# 4040M_V1_0.net
KiCad netlist of a schematic drawn in EasyEDA Pro
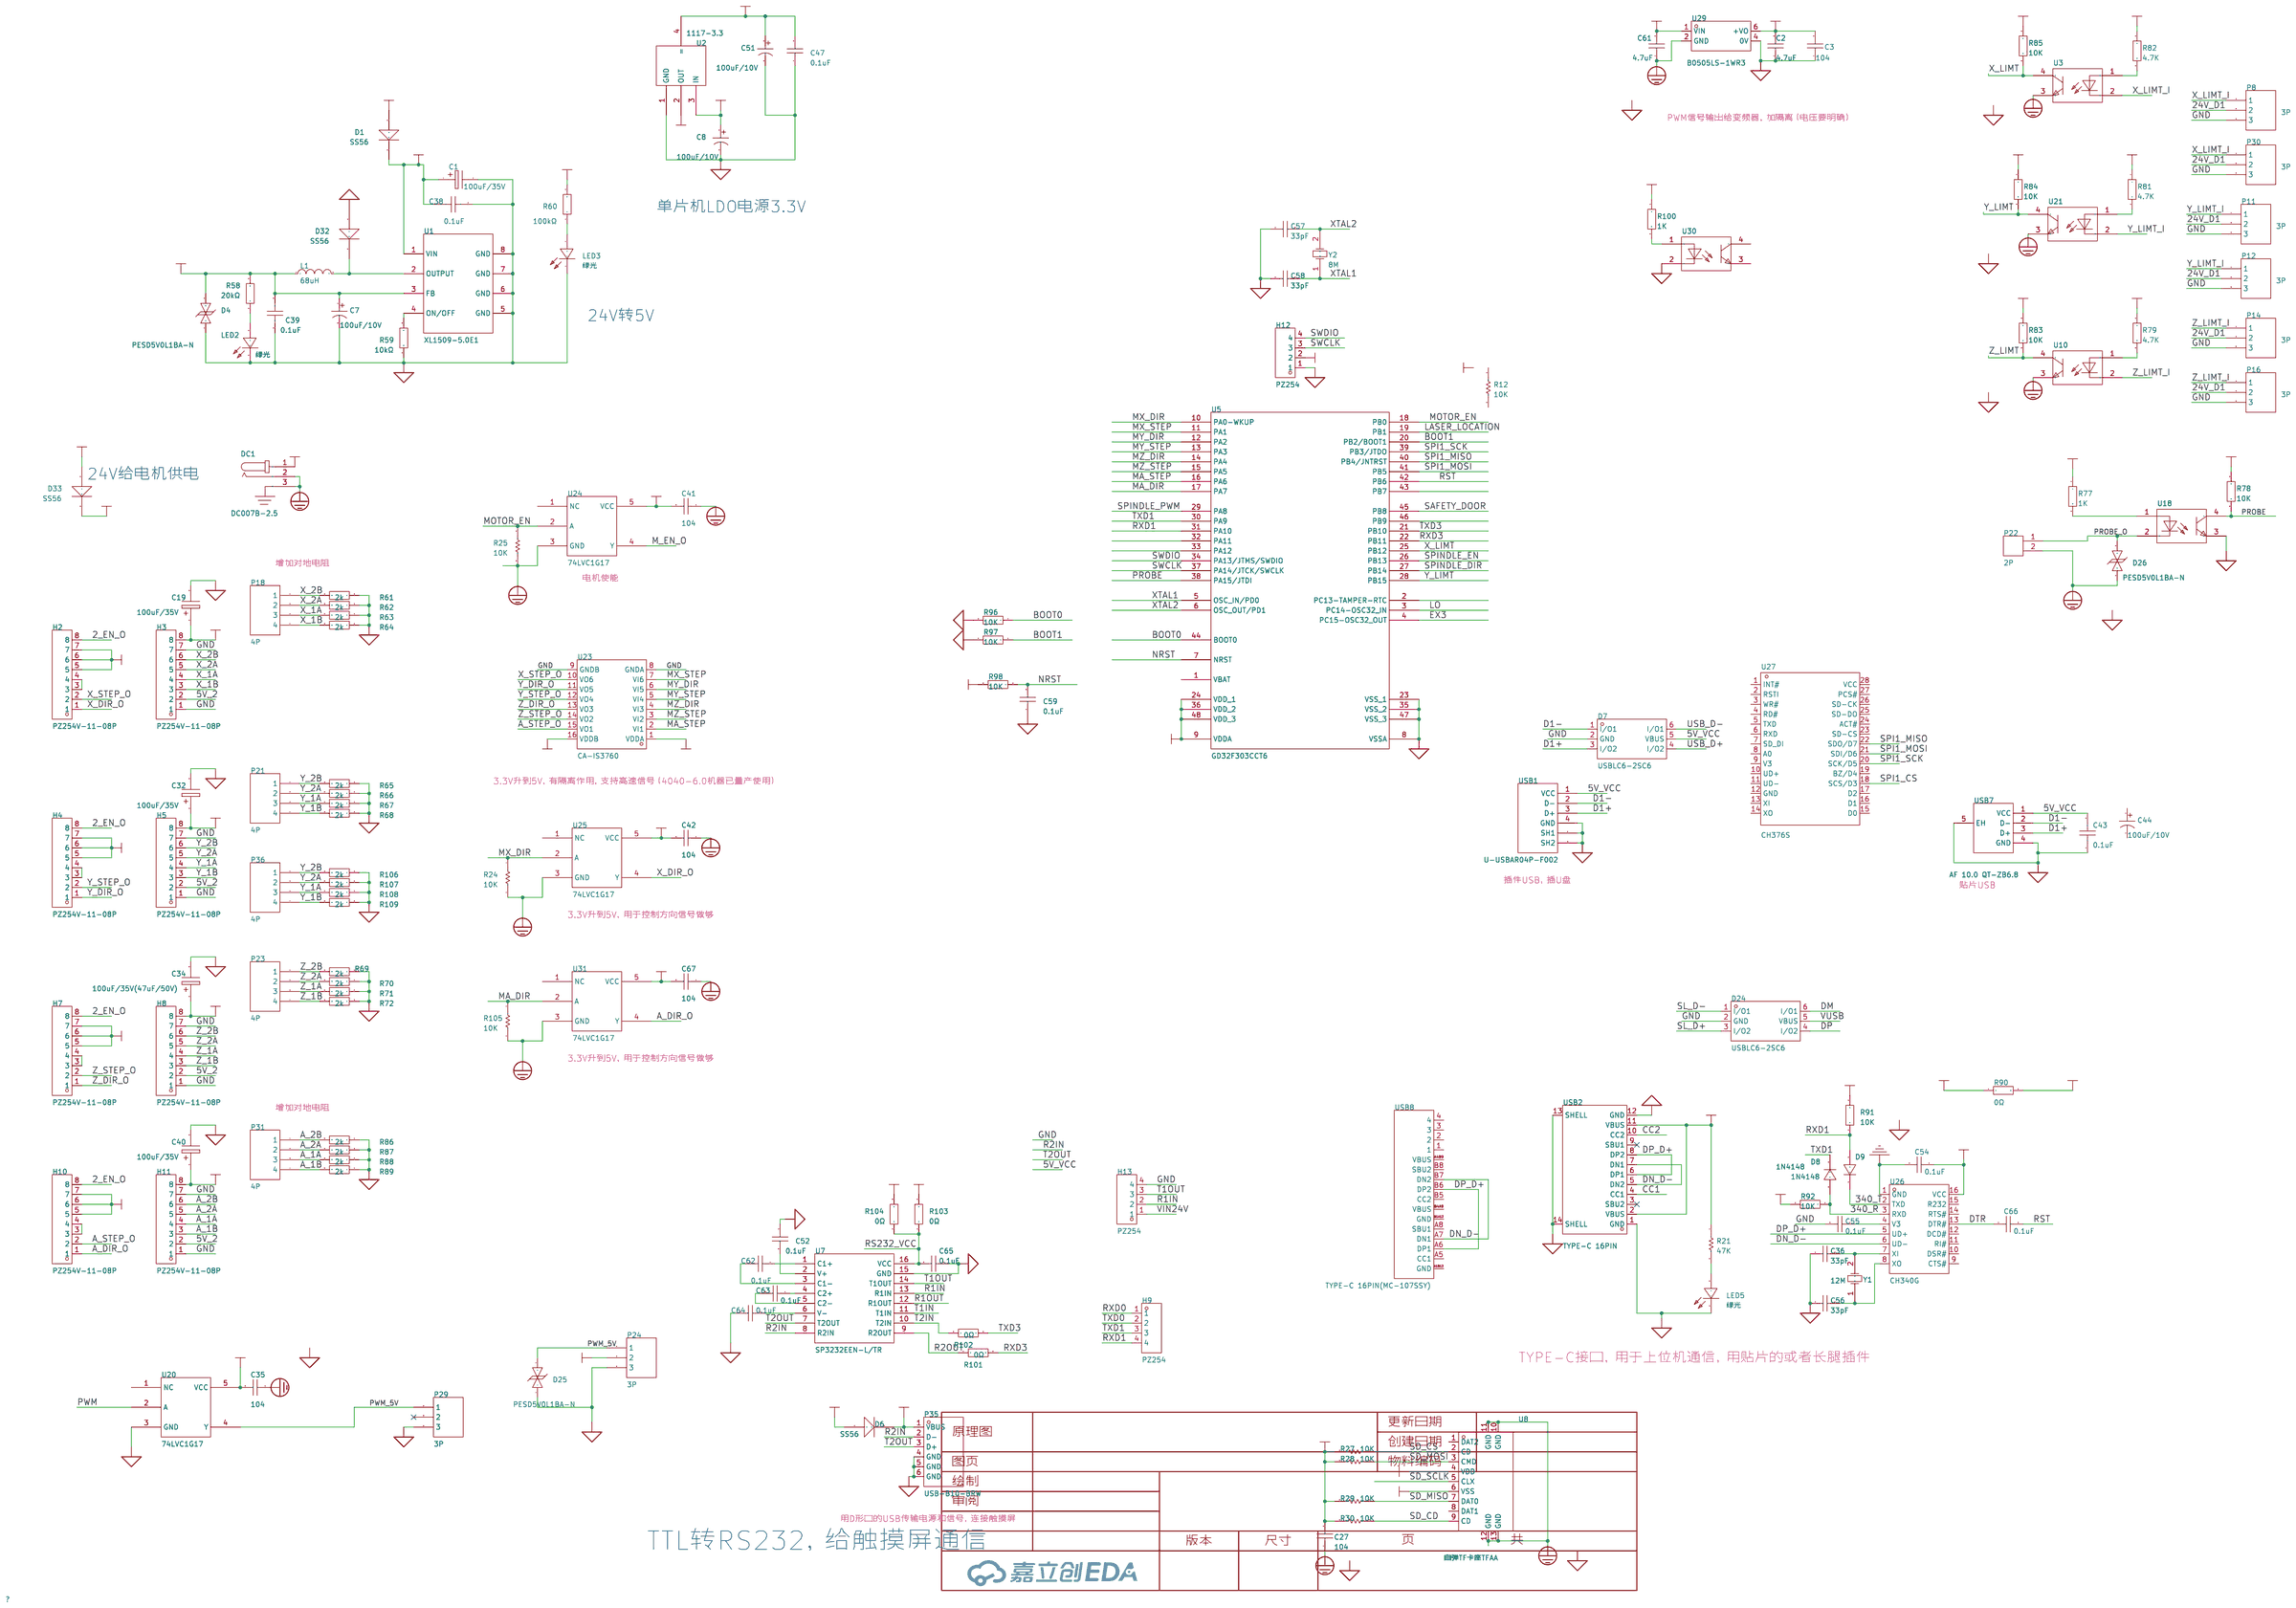
[diagram p0: schematic sheet]

(export (version "E")
  (design (tool "Eeschema 10.0.6"))
  (components
    (comp (ref "C1")
      (value "100uF/35V")
      (footprint "easyedapro:电解电容贴片10x10")
      (libsource (lib "easyedapro") (part "ELECTRO1"))
    )
    (comp (ref "C2") (value "4.7uF") (libsource (lib "easyedapro") (part "CAP")))
    (comp (ref "C3") (value "104") (libsource (lib "easyedapro") (part "CAP")))
    (comp (ref "C7")
      (value "100uF/10V")
      (footprint "easyedapro:CAP-SMD_BD5.0-L5.3-W5.3-RD")
      (fields (field (name "Manufacturer Part") "CS1A101M-CRD54") (field (name "Manufacturer") "ST(先科)"))
      (libsource (lib "easyedapro") (part "CS1A101M-CRD54"))
    )
    (comp (ref "C8")
      (value "100uF/10V")
      (footprint "easyedapro:CAP-SMD_BD5.0-L5.3-W5.3-RD")
      (fields (field (name "Manufacturer Part") "CS1A101M-CRD54") (field (name "Manufacturer") "ST(先科)"))
      (libsource (lib "easyedapro") (part "CS1A101M-CRD54"))
    )
    (comp (ref "C19")
      (value "100uF/35V")
      (footprint "easyedapro:电解电容贴片10x10")
      (libsource (lib "easyedapro") (part "ELECTRO1"))
    )
    (comp (ref "C27")
      (value "104")
      (footprint "easyedapro:11")
      (description "Capacitor (Semiconductor SIM Model)")
      (libsource (lib "easyedapro") (part "Cap Semi"))
    )
    (comp (ref "C32")
      (value "100uF/35V")
      (footprint "easyedapro:电解电容贴片10x10")
      (libsource (lib "easyedapro") (part "ELECTRO1"))
    )
    (comp (ref "C34")
      (value "100uF/35V(47uF/50V)")
      (footprint "easyedapro:电解电容贴片10x10")
      (libsource (lib "easyedapro") (part "ELECTRO1"))
    )
    (comp (ref "C35")
      (value "104")
      (footprint "easyedapro:0603C")
      (description "Capacitor (Semiconductor SIM Model)")
      (libsource (lib "easyedapro") (part "Cap Semi"))
    )
    (comp (ref "C36")
      (value "33pF")
      (footprint "easyedapro:C0603")
      (description "容值:12pF;精度:±5%;额定电压:50V;温度系数:C0G;")
      (fields
        (field (name "Manufacturer Part") "CL10C120JB8NNNC")
        (field (name "Manufacturer") "SAMSUNG(三星)")
      )
      (libsource (lib "easyedapro") (part "CL10C120JB8NNNC"))
    )
    (comp (ref "C38")
      (value "0.1uF")
      (footprint "easyedapro:C0603")
      (description "容值:8.2nF;精度:±10%;额定电压:50V;温度系数:X7R;")
      (fields (field (name "Manufacturer Part") "0603B822K500NT") (field (name "Manufacturer") "FH(风华)"))
      (libsource (lib "easyedapro") (part "0603B822K500NT"))
    )
    (comp (ref "C39")
      (value "0.1uF")
      (footprint "easyedapro:C0603")
      (description "容值:8.2nF;精度:±10%;额定电压:50V;温度系数:X7R;")
      (fields (field (name "Manufacturer Part") "0603B822K500NT") (field (name "Manufacturer") "FH(风华)"))
      (libsource (lib "easyedapro") (part "0603B822K500NT"))
    )
    (comp (ref "C40")
      (value "100uF/35V")
      (footprint "easyedapro:电解电容贴片10x10")
      (libsource (lib "easyedapro") (part "ELECTRO1"))
    )
    (comp (ref "C41")
      (value "104")
      (footprint "easyedapro:0603C")
      (description "Capacitor (Semiconductor SIM Model)")
      (libsource (lib "easyedapro") (part "Cap Semi"))
    )
    (comp (ref "C42")
      (value "104")
      (footprint "easyedapro:0603C")
      (description "Capacitor (Semiconductor SIM Model)")
      (libsource (lib "easyedapro") (part "Cap Semi"))
    )
    (comp (ref "C43")
      (value "0.1uF")
      (footprint "easyedapro:C0603")
      (description "容值:8.2nF;精度:±10%;额定电压:50V;温度系数:X7R;")
      (fields (field (name "Manufacturer Part") "0603B822K500NT") (field (name "Manufacturer") "FH(风华)"))
      (libsource (lib "easyedapro") (part "0603B822K500NT"))
    )
    (comp (ref "C44")
      (value "100uF/10V")
      (footprint "easyedapro:CAP-SMD_BD5.0-L5.3-W5.3-RD")
      (fields (field (name "Manufacturer Part") "CS1A101M-CRD54") (field (name "Manufacturer") "ST(先科)"))
      (libsource (lib "easyedapro") (part "CS1A101M-CRD54"))
    )
    (comp (ref "C47")
      (value "0.1uF")
      (footprint "easyedapro:C0603")
      (description "容值:6.8nF;精度:±10%;额定电压:50V;温度系数:X7R;")
      (fields (field (name "Manufacturer Part") "0603B682K500NT") (field (name "Manufacturer") "FH(风华)"))
      (libsource (lib "easyedapro") (part "0603B682K500NT"))
    )
    (comp (ref "C51")
      (value "100uF/10V")
      (footprint "easyedapro:CAP-SMD_BD5.0-L5.3-W5.3-RD")
      (fields (field (name "Manufacturer Part") "CS1A101M-CRD54") (field (name "Manufacturer") "ST(先科)"))
      (libsource (lib "easyedapro") (part "CS1A101M-CRD54"))
    )
    (comp (ref "C52")
      (value "0.1uF")
      (footprint "easyedapro:C0603")
      (description "容值:6.8nF;精度:±10%;额定电压:50V;温度系数:X7R;")
      (fields (field (name "Manufacturer Part") "0603B682K500NT") (field (name "Manufacturer") "FH(风华)"))
      (libsource (lib "easyedapro") (part "0603B682K500NT"))
    )
    (comp (ref "C54")
      (value "0.1uF")
      (footprint "easyedapro:C0603")
      (description "容值:6.8nF;精度:±10%;额定电压:50V;温度系数:X7R;")
      (fields (field (name "Manufacturer Part") "0603B682K500NT") (field (name "Manufacturer") "FH(风华)"))
      (libsource (lib "easyedapro") (part "0603B682K500NT"))
    )
    (comp (ref "C55")
      (value "0.1uF")
      (footprint "easyedapro:C0603")
      (description "容值:6.8nF;精度:±10%;额定电压:50V;温度系数:X7R;")
      (fields (field (name "Manufacturer Part") "0603B682K500NT") (field (name "Manufacturer") "FH(风华)"))
      (libsource (lib "easyedapro") (part "0603B682K500NT"))
    )
    (comp (ref "C56")
      (value "33pF")
      (footprint "easyedapro:C0603")
      (description "容值:12pF;精度:±5%;额定电压:50V;温度系数:C0G;")
      (fields
        (field (name "Manufacturer Part") "CL10C120JB8NNNC")
        (field (name "Manufacturer") "SAMSUNG(三星)")
      )
      (libsource (lib "easyedapro") (part "CL10C120JB8NNNC"))
    )
    (comp (ref "C57")
      (value "33pF")
      (footprint "easyedapro:C0603")
      (description "容值:12pF;精度:±5%;额定电压:50V;温度系数:C0G;")
      (fields
        (field (name "Manufacturer Part") "CL10C120JB8NNNC")
        (field (name "Manufacturer") "SAMSUNG(三星)")
      )
      (libsource (lib "easyedapro") (part "CL10C120JB8NNNC"))
    )
    (comp (ref "C58")
      (value "33pF")
      (footprint "easyedapro:C0603")
      (description "容值:12pF;精度:±5%;额定电压:50V;温度系数:C0G;")
      (fields
        (field (name "Manufacturer Part") "CL10C120JB8NNNC")
        (field (name "Manufacturer") "SAMSUNG(三星)")
      )
      (libsource (lib "easyedapro") (part "CL10C120JB8NNNC"))
    )
    (comp (ref "C59")
      (value "0.1uF")
      (footprint "easyedapro:C0603")
      (description "容值:6.8nF;精度:±10%;额定电压:50V;温度系数:X7R;")
      (fields (field (name "Manufacturer Part") "0603B682K500NT") (field (name "Manufacturer") "FH(风华)"))
      (libsource (lib "easyedapro") (part "0603B682K500NT"))
    )
    (comp (ref "C61") (value "4.7uF") (libsource (lib "easyedapro") (part "CAP")))
    (comp (ref "C62")
      (value "0.1uF")
      (footprint "easyedapro:C0603")
      (description "容值:6.8nF;精度:±10%;额定电压:50V;温度系数:X7R;")
      (fields (field (name "Manufacturer Part") "0603B682K500NT") (field (name "Manufacturer") "FH(风华)"))
      (libsource (lib "easyedapro") (part "0603B682K500NT"))
    )
    (comp (ref "C63")
      (value "0.1uF")
      (footprint "easyedapro:C0603")
      (description "容值:6.8nF;精度:±10%;额定电压:50V;温度系数:X7R;")
      (fields (field (name "Manufacturer Part") "0603B682K500NT") (field (name "Manufacturer") "FH(风华)"))
      (libsource (lib "easyedapro") (part "0603B682K500NT"))
    )
    (comp (ref "C64")
      (value "0.1uF")
      (footprint "easyedapro:C0603")
      (description "容值:6.8nF;精度:±10%;额定电压:50V;温度系数:X7R;")
      (fields (field (name "Manufacturer Part") "0603B682K500NT") (field (name "Manufacturer") "FH(风华)"))
      (libsource (lib "easyedapro") (part "0603B682K500NT"))
    )
    (comp (ref "C65")
      (value "0.1uF")
      (footprint "easyedapro:C0603")
      (description "容值:6.8nF;精度:±10%;额定电压:50V;温度系数:X7R;")
      (fields (field (name "Manufacturer Part") "0603B682K500NT") (field (name "Manufacturer") "FH(风华)"))
      (libsource (lib "easyedapro") (part "0603B682K500NT"))
    )
    (comp (ref "C66")
      (value "0.1uF")
      (footprint "easyedapro:C0603")
      (description "容值:6.8nF;精度:±10%;额定电压:50V;温度系数:X7R;")
      (fields (field (name "Manufacturer Part") "0603B682K500NT") (field (name "Manufacturer") "FH(风华)"))
      (libsource (lib "easyedapro") (part "0603B682K500NT"))
    )
    (comp (ref "C67")
      (value "104")
      (footprint "easyedapro:0603C")
      (description "Capacitor (Semiconductor SIM Model)")
      (libsource (lib "easyedapro") (part "Cap Semi"))
    )
    (comp (ref "D1")
      (value "SS56")
      (footprint "easyedapro:SMA")
      (libsource (lib "easyedapro") (part "1N4148"))
    )
    (comp (ref "D4")
      (value "PESD5V0L1BA-N")
      (footprint "easyedapro:SOD-523_L1.2-W0.8-LS1.6-BI")
      (description "极性:Bidirectional;反向关断电压（典型值）:5V (Max);击穿电压（最小值）:6V;箝位电压:15V;峰值脉冲电流（10/1000us）:5A (8/20us);")
      (fields (field (name "Manufacturer") "BORN伯恩半导体"))
      (libsource (lib "easyedapro") (part "PESD5V0S1BBN"))
    )
    (comp (ref "D6")
      (value "SS56")
      (footprint "easyedapro:SMA")
      (libsource (lib "easyedapro") (part "1N4148"))
    )
    (comp (ref "D7")
      (value "USBLC6-2SC6")
      (footprint "easyedapro:SOT-23-6_L2.9-W1.6-P0.95-LS2.8-BL")
      (description "最大钳位电压:15V;击穿电压:6V;")
      (fields (field (name "Manufacturer") "UMW(友台半导体)"))
      (libsource (lib "easyedapro") (part "USBLC6-2SC6_C2687116"))
    )
    (comp (ref "D8")
      (value "1N4148")
      (footprint "easyedapro:SOD-323_L1.8-W1.3-LS2.5-RD")
      (description "二极管配置:独立式;正向压降(Vf):1.25V@150mA;直流反向耐压(Vr):100V;整流电流:150mA;反向恢复时间(Trr):4ns;")
      (fields (field (name "Manufacturer") "CJ(江苏长电/长晶)"))
      (libsource (lib "easyedapro") (part "1N4148WS T4"))
    )
    (comp (ref "D9")
      (value "1N4148")
      (footprint "easyedapro:SOD-323_L1.8-W1.3-LS2.5-RD")
      (description "二极管配置:独立式;正向压降(Vf):1.25V@150mA;直流反向耐压(Vr):100V;整流电流:150mA;反向恢复时间(Trr):4ns;")
      (fields (field (name "Manufacturer") "CJ(江苏长电/长晶)"))
      (libsource (lib "easyedapro") (part "1N4148WS T4"))
    )
    (comp (ref "D24")
      (value "USBLC6-2SC6")
      (footprint "easyedapro:SOT-23-6_L2.9-W1.6-P0.95-LS2.8-BL")
      (description "最大钳位电压:15V;击穿电压:6V;")
      (fields (field (name "Manufacturer") "UMW(友台半导体)"))
      (libsource (lib "easyedapro") (part "USBLC6-2SC6_C2687116"))
    )
    (comp (ref "D25")
      (value "PESD5V0L1BA-N")
      (footprint "easyedapro:SOD-523_L1.2-W0.8-LS1.6-BI")
      (description "极性:Bidirectional;反向关断电压（典型值）:5V (Max);击穿电压（最小值）:6V;箝位电压:15V;峰值脉冲电流（10/1000us）:5A (8/20us);")
      (fields (field (name "Manufacturer") "BORN伯恩半导体"))
      (libsource (lib "easyedapro") (part "PESD5V0S1BBN"))
    )
    (comp (ref "D26")
      (value "PESD5V0L1BA-N")
      (footprint "easyedapro:SOD-523_L1.2-W0.8-LS1.6-BI")
      (description "极性:Bidirectional;反向关断电压（典型值）:5V (Max);击穿电压（最小值）:6V;箝位电压:15V;峰值脉冲电流（10/1000us）:5A (8/20us);")
      (fields (field (name "Manufacturer") "BORN伯恩半导体"))
      (libsource (lib "easyedapro") (part "PESD5V0S1BBN"))
    )
    (comp (ref "D32")
      (value "SS56")
      (footprint "easyedapro:SMA")
      (libsource (lib "easyedapro") (part "1N4148"))
    )
    (comp (ref "D33")
      (value "SS56")
      (footprint "easyedapro:SMA")
      (libsource (lib "easyedapro") (part "1N4148"))
    )
    (comp (ref "DC1")
      (value "DC007B-2.5")
      (footprint "easyedapro:DC-IN-TH_HX-DC007B-2.5")
      (description "连接器类型:DC电源插座;安装方式:弯插;触点内径:2.5mm;触点外径:7.7mm;额定电流:5A;额定电压:20V;工作温度:-25°C~+70°C;")
      (fields (field (name "Manufacturer") "SHOU HAN(首韩)"))
      (libsource (lib "easyedapro") (part "DC007B-2.5"))
    )
    (comp (ref "H2")
      (value "PZ254V-11-08P")
      (footprint "easyedapro:HDR-TH_8P-P2.54-V-M")
      (fields (field (name "Manufacturer") "XFCN(兴飞)"))
      (libsource (lib "easyedapro") (part "PZ254V-11-08P"))
    )
    (comp (ref "H3")
      (value "PZ254V-11-08P")
      (footprint "easyedapro:HDR-TH_8P-P2.54-V-M")
      (fields (field (name "Manufacturer") "XFCN(兴飞)"))
      (libsource (lib "easyedapro") (part "PZ254V-11-08P"))
    )
    (comp (ref "H4")
      (value "PZ254V-11-08P")
      (footprint "easyedapro:HDR-TH_8P-P2.54-V-M")
      (fields (field (name "Manufacturer") "XFCN(兴飞)"))
      (libsource (lib "easyedapro") (part "PZ254V-11-08P"))
    )
    (comp (ref "H5")
      (value "PZ254V-11-08P")
      (footprint "easyedapro:HDR-TH_8P-P2.54-V-M")
      (fields (field (name "Manufacturer") "XFCN(兴飞)"))
      (libsource (lib "easyedapro") (part "PZ254V-11-08P"))
    )
    (comp (ref "H7")
      (value "PZ254V-11-08P")
      (footprint "easyedapro:HDR-TH_8P-P2.54-V-M")
      (fields (field (name "Manufacturer") "XFCN(兴飞)"))
      (libsource (lib "easyedapro") (part "PZ254V-11-08P"))
    )
    (comp (ref "H8")
      (value "PZ254V-11-08P")
      (footprint "easyedapro:HDR-TH_8P-P2.54-V-M")
      (fields (field (name "Manufacturer") "XFCN(兴飞)"))
      (libsource (lib "easyedapro") (part "PZ254V-11-08P"))
    )
    (comp (ref "H9")
      (value "PZ254")
      (footprint "easyedapro:HDR-TH_4P-P2.54-V-M")
      (fields (field (name "Manufacturer") "XFCN(兴飞)"))
      (libsource (lib "easyedapro") (part "PZ254V-11-04P_C2691448"))
    )
    (comp (ref "H10")
      (value "PZ254V-11-08P")
      (footprint "easyedapro:HDR-TH_8P-P2.54-V-M")
      (fields (field (name "Manufacturer") "XFCN(兴飞)"))
      (libsource (lib "easyedapro") (part "PZ254V-11-08P"))
    )
    (comp (ref "H11")
      (value "PZ254V-11-08P")
      (footprint "easyedapro:HDR-TH_8P-P2.54-V-M")
      (fields (field (name "Manufacturer") "XFCN(兴飞)"))
      (libsource (lib "easyedapro") (part "PZ254V-11-08P"))
    )
    (comp (ref "H12")
      (value "PZ254")
      (footprint "easyedapro:HDR-TH_4P-P2.54-V-M")
      (fields (field (name "Manufacturer") "XFCN(兴飞)"))
      (libsource (lib "easyedapro") (part "PZ254V-11-04P_C2691448"))
    )
    (comp (ref "H13")
      (value "PZ254")
      (footprint "easyedapro:HDR-TH_4P-P2.54-V-M")
      (fields (field (name "Manufacturer") "XFCN(兴飞)"))
      (libsource (lib "easyedapro") (part "PZ254V-11-04P_C2691448"))
    )
    (comp (ref "L1")
      (value "68uH")
      (footprint "easyedapro:IND-SMD_L7.0-W7.0_SMDRI74-330MT")
      (description "电感值:33uH;精度:±20%;额定电流:960mA;饱和电流(Isat):1.8A;类型:屏蔽电感;")
      (fields (field (name "Manufacturer Part") "SMDRI74-330MT") (field (name "Manufacturer") "SXN(顺翔诺)"))
      (libsource (lib "easyedapro") (part "SMDRI74-330MT"))
    )
    (comp (ref "LED2")
      (value "绿光")
      (footprint "easyedapro:LED0603-RD")
      (fields (field (name "Manufacturer") "KENTO"))
      (libsource (lib "easyedapro") (part "KT-0603R"))
    )
    (comp (ref "LED3")
      (value "绿光")
      (footprint "easyedapro:LED0603-RD")
      (fields (field (name "Manufacturer") "KENTO"))
      (libsource (lib "easyedapro") (part "KT-0603R"))
    )
    (comp (ref "LED5")
      (value "绿光")
      (footprint "easyedapro:LED0603-RD")
      (fields (field (name "Manufacturer") "KENTO"))
      (libsource (lib "easyedapro") (part "KT-0603R"))
    )
    (comp (ref "P8")
      (value "3P")
      (footprint "easyedapro:HDR1X3_CON")
      (libsource (lib "easyedapro") (part "3P"))
    )
    (comp (ref "P11")
      (value "3P")
      (footprint "easyedapro:HDR1X3_CON")
      (libsource (lib "easyedapro") (part "3P"))
    )
    (comp (ref "P12")
      (value "3P")
      (footprint "easyedapro:HDR1X3_CON")
      (libsource (lib "easyedapro") (part "3P"))
    )
    (comp (ref "P14")
      (value "3P")
      (footprint "easyedapro:HDR1X3_CON")
      (libsource (lib "easyedapro") (part "3P"))
    )
    (comp (ref "P16")
      (value "3P")
      (footprint "easyedapro:HDR1X3_CON")
      (libsource (lib "easyedapro") (part "3P"))
    )
    (comp (ref "P18")
      (value "4P")
      (footprint "easyedapro:HDR1X4_CON")
      (libsource (lib "easyedapro") (part "4P"))
    )
    (comp (ref "P21")
      (value "4P")
      (footprint "easyedapro:HDR1X4_CON")
      (libsource (lib "easyedapro") (part "4P"))
    )
    (comp (ref "P22") (value "2P") (libsource (lib "easyedapro") (part "2P")))
    (comp (ref "P23")
      (value "4P")
      (footprint "easyedapro:HDR1X4_CON")
      (libsource (lib "easyedapro") (part "4P"))
    )
    (comp (ref "P24")
      (value "3P")
      (footprint "easyedapro:HDR1X3_CON")
      (libsource (lib "easyedapro") (part "3P"))
    )
    (comp (ref "P29")
      (value "3P")
      (footprint "easyedapro:HDR1X3_CON")
      (libsource (lib "easyedapro") (part "3P"))
    )
    (comp (ref "P30")
      (value "3P")
      (footprint "easyedapro:HDR1X3_CON")
      (libsource (lib "easyedapro") (part "3P"))
    )
    (comp (ref "P31")
      (value "4P")
      (footprint "easyedapro:HDR1X4_CON")
      (libsource (lib "easyedapro") (part "4P"))
    )
    (comp (ref "P35")
      (value "USB-B10-BRW")
      (footprint "easyedapro:USB-B-TH_USB-B10-BRW")
      (fields (field (name "Manufacturer") "XUNPU(讯普)"))
      (libsource (lib "easyedapro") (part "USB-B10-BRW"))
    )
    (comp (ref "P36")
      (value "4P")
      (footprint "easyedapro:HDR1X4_CON")
      (libsource (lib "easyedapro") (part "4P"))
    )
    (comp (ref "R12")
      (value "10K")
      (footprint "easyedapro:0603R")
      (description "Resistor")
      (libsource (lib "") (part "RES_1"))
    )
    (comp (ref "R21")
      (value "47K")
      (footprint "easyedapro:10")
      (description "Resistor")
      (libsource (lib "") (part "RES_1"))
    )
    (comp (ref "R24")
      (value "10K")
      (description "Resistor")
      (fields (field (name "Publisher") "Altium Limited"))
      (libsource (lib "easyedapro") (part "RES"))
    )
    (comp (ref "R25")
      (value "10K")
      (description "Resistor")
      (fields (field (name "Publisher") "Altium Limited"))
      (libsource (lib "easyedapro") (part "RES"))
    )
    (comp (ref "R27")
      (value "10K")
      (footprint "easyedapro:10")
      (description "Resistor")
      (libsource (lib "") (part "RES_1"))
    )
    (comp (ref "R28")
      (value "10K")
      (footprint "easyedapro:10")
      (description "Resistor")
      (libsource (lib "") (part "RES_1"))
    )
    (comp (ref "R29")
      (value "10K")
      (footprint "easyedapro:10")
      (description "Resistor")
      (libsource (lib "") (part "RES_1"))
    )
    (comp (ref "R30")
      (value "10K")
      (footprint "easyedapro:10")
      (description "Resistor")
      (libsource (lib "") (part "RES_1"))
    )
    (comp (ref "R58")
      (value "20kΩ")
      (footprint "easyedapro:R0603")
      (description "电阻类型:厚膜电阻;阻值:24kΩ;精度:±1%;功率:100mW;工作电压:75V;温度系数:±100ppm/°C;")
      (fields
        (field (name "Manufacturer Part") "0603WAF2402T5E")
        (field (name "Manufacturer") "UNI-ROYAL(厚声)")
      )
      (libsource (lib "easyedapro") (part "0603WAF2402T5E"))
    )
    (comp (ref "R59")
      (value "10kΩ")
      (footprint "easyedapro:R0603")
      (description "电阻类型:厚膜电阻;阻值:24kΩ;精度:±1%;功率:100mW;工作电压:75V;温度系数:±100ppm/°C;")
      (fields
        (field (name "Manufacturer Part") "0603WAF2402T5E")
        (field (name "Manufacturer") "UNI-ROYAL(厚声)")
      )
      (libsource (lib "easyedapro") (part "0603WAF2402T5E"))
    )
    (comp (ref "R60")
      (value "100kΩ")
      (footprint "easyedapro:R0603")
      (description "电阻类型:厚膜电阻;阻值:24kΩ;精度:±1%;功率:100mW;工作电压:75V;温度系数:±100ppm/°C;")
      (fields
        (field (name "Manufacturer Part") "0603WAF2402T5E")
        (field (name "Manufacturer") "UNI-ROYAL(厚声)")
      )
      (libsource (lib "easyedapro") (part "0603WAF2402T5E"))
    )
    (comp (ref "R61")
      (value "2k")
      (footprint "easyedapro:R0603")
      (description "电阻类型:厚膜电阻;阻值:24kΩ;精度:±1%;功率:100mW;工作电压:75V;温度系数:±100ppm/°C;")
      (fields
        (field (name "Manufacturer Part") "0603WAF2402T5E")
        (field (name "Manufacturer") "UNI-ROYAL(厚声)")
      )
      (libsource (lib "easyedapro") (part "0603WAF2402T5E"))
    )
    (comp (ref "R62")
      (value "2k")
      (footprint "easyedapro:R0603")
      (description "电阻类型:厚膜电阻;阻值:24kΩ;精度:±1%;功率:100mW;工作电压:75V;温度系数:±100ppm/°C;")
      (fields
        (field (name "Manufacturer Part") "0603WAF2402T5E")
        (field (name "Manufacturer") "UNI-ROYAL(厚声)")
      )
      (libsource (lib "easyedapro") (part "0603WAF2402T5E"))
    )
    (comp (ref "R63")
      (value "2k")
      (footprint "easyedapro:R0603")
      (description "电阻类型:厚膜电阻;阻值:24kΩ;精度:±1%;功率:100mW;工作电压:75V;温度系数:±100ppm/°C;")
      (fields
        (field (name "Manufacturer Part") "0603WAF2402T5E")
        (field (name "Manufacturer") "UNI-ROYAL(厚声)")
      )
      (libsource (lib "easyedapro") (part "0603WAF2402T5E"))
    )
    (comp (ref "R64")
      (value "2k")
      (footprint "easyedapro:R0603")
      (description "电阻类型:厚膜电阻;阻值:24kΩ;精度:±1%;功率:100mW;工作电压:75V;温度系数:±100ppm/°C;")
      (fields
        (field (name "Manufacturer Part") "0603WAF2402T5E")
        (field (name "Manufacturer") "UNI-ROYAL(厚声)")
      )
      (libsource (lib "easyedapro") (part "0603WAF2402T5E"))
    )
    (comp (ref "R65")
      (value "2k")
      (footprint "easyedapro:R0603")
      (description "电阻类型:厚膜电阻;阻值:24kΩ;精度:±1%;功率:100mW;工作电压:75V;温度系数:±100ppm/°C;")
      (fields
        (field (name "Manufacturer Part") "0603WAF2402T5E")
        (field (name "Manufacturer") "UNI-ROYAL(厚声)")
      )
      (libsource (lib "easyedapro") (part "0603WAF2402T5E"))
    )
    (comp (ref "R66")
      (value "2k")
      (footprint "easyedapro:R0603")
      (description "电阻类型:厚膜电阻;阻值:24kΩ;精度:±1%;功率:100mW;工作电压:75V;温度系数:±100ppm/°C;")
      (fields
        (field (name "Manufacturer Part") "0603WAF2402T5E")
        (field (name "Manufacturer") "UNI-ROYAL(厚声)")
      )
      (libsource (lib "easyedapro") (part "0603WAF2402T5E"))
    )
    (comp (ref "R67")
      (value "2k")
      (footprint "easyedapro:R0603")
      (description "电阻类型:厚膜电阻;阻值:24kΩ;精度:±1%;功率:100mW;工作电压:75V;温度系数:±100ppm/°C;")
      (fields
        (field (name "Manufacturer Part") "0603WAF2402T5E")
        (field (name "Manufacturer") "UNI-ROYAL(厚声)")
      )
      (libsource (lib "easyedapro") (part "0603WAF2402T5E"))
    )
    (comp (ref "R68")
      (value "2k")
      (footprint "easyedapro:R0603")
      (description "电阻类型:厚膜电阻;阻值:24kΩ;精度:±1%;功率:100mW;工作电压:75V;温度系数:±100ppm/°C;")
      (fields
        (field (name "Manufacturer Part") "0603WAF2402T5E")
        (field (name "Manufacturer") "UNI-ROYAL(厚声)")
      )
      (libsource (lib "easyedapro") (part "0603WAF2402T5E"))
    )
    (comp (ref "R69")
      (value "2k")
      (footprint "easyedapro:R0603")
      (description "电阻类型:厚膜电阻;阻值:24kΩ;精度:±1%;功率:100mW;工作电压:75V;温度系数:±100ppm/°C;")
      (fields
        (field (name "Manufacturer Part") "0603WAF2402T5E")
        (field (name "Manufacturer") "UNI-ROYAL(厚声)")
      )
      (libsource (lib "easyedapro") (part "0603WAF2402T5E"))
    )
    (comp (ref "R70")
      (value "2k")
      (footprint "easyedapro:R0603")
      (description "电阻类型:厚膜电阻;阻值:24kΩ;精度:±1%;功率:100mW;工作电压:75V;温度系数:±100ppm/°C;")
      (fields
        (field (name "Manufacturer Part") "0603WAF2402T5E")
        (field (name "Manufacturer") "UNI-ROYAL(厚声)")
      )
      (libsource (lib "easyedapro") (part "0603WAF2402T5E"))
    )
    (comp (ref "R71")
      (value "2k")
      (footprint "easyedapro:R0603")
      (description "电阻类型:厚膜电阻;阻值:24kΩ;精度:±1%;功率:100mW;工作电压:75V;温度系数:±100ppm/°C;")
      (fields
        (field (name "Manufacturer Part") "0603WAF2402T5E")
        (field (name "Manufacturer") "UNI-ROYAL(厚声)")
      )
      (libsource (lib "easyedapro") (part "0603WAF2402T5E"))
    )
    (comp (ref "R72")
      (value "2k")
      (footprint "easyedapro:R0603")
      (description "电阻类型:厚膜电阻;阻值:24kΩ;精度:±1%;功率:100mW;工作电压:75V;温度系数:±100ppm/°C;")
      (fields
        (field (name "Manufacturer Part") "0603WAF2402T5E")
        (field (name "Manufacturer") "UNI-ROYAL(厚声)")
      )
      (libsource (lib "easyedapro") (part "0603WAF2402T5E"))
    )
    (comp (ref "R77")
      (value "1K")
      (footprint "easyedapro:R0603")
      (description "电阻类型:厚膜电阻;阻值:24kΩ;精度:±1%;功率:100mW;工作电压:75V;温度系数:±100ppm/°C;")
      (fields
        (field (name "Manufacturer Part") "0603WAF2402T5E")
        (field (name "Manufacturer") "UNI-ROYAL(厚声)")
      )
      (libsource (lib "easyedapro") (part "0603WAF2402T5E"))
    )
    (comp (ref "R78")
      (value "10K")
      (footprint "easyedapro:R0603")
      (description "电阻类型:厚膜电阻;阻值:24kΩ;精度:±1%;功率:100mW;工作电压:75V;温度系数:±100ppm/°C;")
      (fields
        (field (name "Manufacturer Part") "0603WAF2402T5E")
        (field (name "Manufacturer") "UNI-ROYAL(厚声)")
      )
      (libsource (lib "easyedapro") (part "0603WAF2402T5E"))
    )
    (comp (ref "R79")
      (value "4.7K")
      (footprint "easyedapro:R0603")
      (description "电阻类型:厚膜电阻;阻值:24kΩ;精度:±1%;功率:100mW;工作电压:75V;温度系数:±100ppm/°C;")
      (fields
        (field (name "Manufacturer Part") "0603WAF2402T5E")
        (field (name "Manufacturer") "UNI-ROYAL(厚声)")
      )
      (libsource (lib "easyedapro") (part "0603WAF2402T5E"))
    )
    (comp (ref "R81")
      (value "4.7K")
      (footprint "easyedapro:R0603")
      (description "电阻类型:厚膜电阻;阻值:24kΩ;精度:±1%;功率:100mW;工作电压:75V;温度系数:±100ppm/°C;")
      (fields
        (field (name "Manufacturer Part") "0603WAF2402T5E")
        (field (name "Manufacturer") "UNI-ROYAL(厚声)")
      )
      (libsource (lib "easyedapro") (part "0603WAF2402T5E"))
    )
    (comp (ref "R82")
      (value "4.7K")
      (footprint "easyedapro:R0603")
      (description "电阻类型:厚膜电阻;阻值:24kΩ;精度:±1%;功率:100mW;工作电压:75V;温度系数:±100ppm/°C;")
      (fields
        (field (name "Manufacturer Part") "0603WAF2402T5E")
        (field (name "Manufacturer") "UNI-ROYAL(厚声)")
      )
      (libsource (lib "easyedapro") (part "0603WAF2402T5E"))
    )
    (comp (ref "R83")
      (value "47K")
      (footprint "easyedapro:R0603")
      (description "电阻类型:厚膜电阻;阻值:24kΩ;精度:±1%;功率:100mW;工作电压:75V;温度系数:±100ppm/°C;")
      (fields
        (field (name "Manufacturer Part") "0603WAF2402T5E")
        (field (name "Manufacturer") "UNI-ROYAL(厚声)")
      )
      (libsource (lib "easyedapro") (part "0603WAF2402T5E"))
    )
    (comp (ref "R84")
      (value "47K")
      (footprint "easyedapro:R0603")
      (description "电阻类型:厚膜电阻;阻值:24kΩ;精度:±1%;功率:100mW;工作电压:75V;温度系数:±100ppm/°C;")
      (fields
        (field (name "Manufacturer Part") "0603WAF2402T5E")
        (field (name "Manufacturer") "UNI-ROYAL(厚声)")
      )
      (libsource (lib "easyedapro") (part "0603WAF2402T5E"))
    )
    (comp (ref "R85")
      (value "47K")
      (footprint "easyedapro:R0603")
      (description "电阻类型:厚膜电阻;阻值:24kΩ;精度:±1%;功率:100mW;工作电压:75V;温度系数:±100ppm/°C;")
      (fields
        (field (name "Manufacturer Part") "0603WAF2402T5E")
        (field (name "Manufacturer") "UNI-ROYAL(厚声)")
      )
      (libsource (lib "easyedapro") (part "0603WAF2402T5E"))
    )
    (comp (ref "R86")
      (value "2k")
      (footprint "easyedapro:R0603")
      (description "电阻类型:厚膜电阻;阻值:24kΩ;精度:±1%;功率:100mW;工作电压:75V;温度系数:±100ppm/°C;")
      (fields
        (field (name "Manufacturer Part") "0603WAF2402T5E")
        (field (name "Manufacturer") "UNI-ROYAL(厚声)")
      )
      (libsource (lib "easyedapro") (part "0603WAF2402T5E"))
    )
    (comp (ref "R87")
      (value "2k")
      (footprint "easyedapro:R0603")
      (description "电阻类型:厚膜电阻;阻值:24kΩ;精度:±1%;功率:100mW;工作电压:75V;温度系数:±100ppm/°C;")
      (fields
        (field (name "Manufacturer Part") "0603WAF2402T5E")
        (field (name "Manufacturer") "UNI-ROYAL(厚声)")
      )
      (libsource (lib "easyedapro") (part "0603WAF2402T5E"))
    )
    (comp (ref "R88")
      (value "2k")
      (footprint "easyedapro:R0603")
      (description "电阻类型:厚膜电阻;阻值:24kΩ;精度:±1%;功率:100mW;工作电压:75V;温度系数:±100ppm/°C;")
      (fields
        (field (name "Manufacturer Part") "0603WAF2402T5E")
        (field (name "Manufacturer") "UNI-ROYAL(厚声)")
      )
      (libsource (lib "easyedapro") (part "0603WAF2402T5E"))
    )
    (comp (ref "R89")
      (value "2k")
      (footprint "easyedapro:R0603")
      (description "电阻类型:厚膜电阻;阻值:24kΩ;精度:±1%;功率:100mW;工作电压:75V;温度系数:±100ppm/°C;")
      (fields
        (field (name "Manufacturer Part") "0603WAF2402T5E")
        (field (name "Manufacturer") "UNI-ROYAL(厚声)")
      )
      (libsource (lib "easyedapro") (part "0603WAF2402T5E"))
    )
    (comp (ref "R90")
      (value "0Ω")
      (footprint "easyedapro:R0603")
      (description "电阻类型:厚膜电阻;阻值:24kΩ;精度:±1%;功率:100mW;工作电压:75V;温度系数:±100ppm/°C;")
      (fields
        (field (name "Manufacturer Part") "0603WAF2402T5E")
        (field (name "Manufacturer") "UNI-ROYAL(厚声)")
      )
      (libsource (lib "easyedapro") (part "0603WAF2402T5E"))
    )
    (comp (ref "R91")
      (value "10K")
      (footprint "easyedapro:R0603")
      (description "电阻类型:厚膜电阻;阻值:24kΩ;精度:±1%;功率:100mW;工作电压:75V;温度系数:±100ppm/°C;")
      (fields
        (field (name "Manufacturer Part") "0603WAF2402T5E")
        (field (name "Manufacturer") "UNI-ROYAL(厚声)")
      )
      (libsource (lib "easyedapro") (part "0603WAF2402T5E"))
    )
    (comp (ref "R92")
      (value "10K")
      (footprint "easyedapro:R0603")
      (description "电阻类型:厚膜电阻;阻值:24kΩ;精度:±1%;功率:100mW;工作电压:75V;温度系数:±100ppm/°C;")
      (fields
        (field (name "Manufacturer Part") "0603WAF2402T5E")
        (field (name "Manufacturer") "UNI-ROYAL(厚声)")
      )
      (libsource (lib "easyedapro") (part "0603WAF2402T5E"))
    )
    (comp (ref "R96")
      (value "10K")
      (footprint "easyedapro:R0603")
      (description "电阻类型:厚膜电阻;阻值:24kΩ;精度:±1%;功率:100mW;工作电压:75V;温度系数:±100ppm/°C;")
      (fields
        (field (name "Manufacturer Part") "0603WAF2402T5E")
        (field (name "Manufacturer") "UNI-ROYAL(厚声)")
      )
      (libsource (lib "easyedapro") (part "0603WAF2402T5E"))
    )
    (comp (ref "R97")
      (value "10K")
      (footprint "easyedapro:R0603")
      (description "电阻类型:厚膜电阻;阻值:24kΩ;精度:±1%;功率:100mW;工作电压:75V;温度系数:±100ppm/°C;")
      (fields
        (field (name "Manufacturer Part") "0603WAF2402T5E")
        (field (name "Manufacturer") "UNI-ROYAL(厚声)")
      )
      (libsource (lib "easyedapro") (part "0603WAF2402T5E"))
    )
    (comp (ref "R98")
      (value "10K")
      (footprint "easyedapro:R0603")
      (description "电阻类型:厚膜电阻;阻值:24kΩ;精度:±1%;功率:100mW;工作电压:75V;温度系数:±100ppm/°C;")
      (fields
        (field (name "Manufacturer Part") "0603WAF2402T5E")
        (field (name "Manufacturer") "UNI-ROYAL(厚声)")
      )
      (libsource (lib "easyedapro") (part "0603WAF2402T5E"))
    )
    (comp (ref "R100")
      (value "47K")
      (footprint "easyedapro:R0603")
      (description "电阻类型:厚膜电阻;阻值:24kΩ;精度:±1%;功率:100mW;工作电压:75V;温度系数:±100ppm/°C;")
      (fields
        (field (name "Manufacturer Part") "0603WAF2402T5E")
        (field (name "Manufacturer") "UNI-ROYAL(厚声)")
      )
      (libsource (lib "easyedapro") (part "0603WAF2402T5E"))
    )
    (comp (ref "R101")
      (value "0Ω")
      (footprint "easyedapro:R0603")
      (description "电阻类型:厚膜电阻;阻值:24kΩ;精度:±1%;功率:100mW;工作电压:75V;温度系数:±100ppm/°C;")
      (fields
        (field (name "Manufacturer Part") "0603WAF2402T5E")
        (field (name "Manufacturer") "UNI-ROYAL(厚声)")
      )
      (libsource (lib "easyedapro") (part "0603WAF2402T5E"))
    )
    (comp (ref "R102")
      (value "0Ω")
      (footprint "easyedapro:R0603")
      (description "电阻类型:厚膜电阻;阻值:24kΩ;精度:±1%;功率:100mW;工作电压:75V;温度系数:±100ppm/°C;")
      (fields
        (field (name "Manufacturer Part") "0603WAF2402T5E")
        (field (name "Manufacturer") "UNI-ROYAL(厚声)")
      )
      (libsource (lib "easyedapro") (part "0603WAF2402T5E"))
    )
    (comp (ref "R103")
      (value "0Ω")
      (footprint "easyedapro:R0603")
      (description "电阻类型:厚膜电阻;阻值:24kΩ;精度:±1%;功率:100mW;工作电压:75V;温度系数:±100ppm/°C;")
      (fields
        (field (name "Manufacturer Part") "0603WAF2402T5E")
        (field (name "Manufacturer") "UNI-ROYAL(厚声)")
      )
      (libsource (lib "easyedapro") (part "0603WAF2402T5E"))
    )
    (comp (ref "R104")
      (value "0Ω")
      (footprint "easyedapro:R0603")
      (description "电阻类型:厚膜电阻;阻值:24kΩ;精度:±1%;功率:100mW;工作电压:75V;温度系数:±100ppm/°C;")
      (fields
        (field (name "Manufacturer Part") "0603WAF2402T5E")
        (field (name "Manufacturer") "UNI-ROYAL(厚声)")
      )
      (libsource (lib "easyedapro") (part "0603WAF2402T5E"))
    )
    (comp (ref "R105")
      (value "10K")
      (description "Resistor")
      (fields (field (name "Publisher") "Altium Limited"))
      (libsource (lib "easyedapro") (part "RES"))
    )
    (comp (ref "R106")
      (value "2k")
      (footprint "easyedapro:R0603")
      (description "电阻类型:厚膜电阻;阻值:24kΩ;精度:±1%;功率:100mW;工作电压:75V;温度系数:±100ppm/°C;")
      (fields
        (field (name "Manufacturer Part") "0603WAF2402T5E")
        (field (name "Manufacturer") "UNI-ROYAL(厚声)")
      )
      (libsource (lib "easyedapro") (part "0603WAF2402T5E"))
    )
    (comp (ref "R107")
      (value "2k")
      (footprint "easyedapro:R0603")
      (description "电阻类型:厚膜电阻;阻值:24kΩ;精度:±1%;功率:100mW;工作电压:75V;温度系数:±100ppm/°C;")
      (fields
        (field (name "Manufacturer Part") "0603WAF2402T5E")
        (field (name "Manufacturer") "UNI-ROYAL(厚声)")
      )
      (libsource (lib "easyedapro") (part "0603WAF2402T5E"))
    )
    (comp (ref "R108")
      (value "2k")
      (footprint "easyedapro:R0603")
      (description "电阻类型:厚膜电阻;阻值:24kΩ;精度:±1%;功率:100mW;工作电压:75V;温度系数:±100ppm/°C;")
      (fields
        (field (name "Manufacturer Part") "0603WAF2402T5E")
        (field (name "Manufacturer") "UNI-ROYAL(厚声)")
      )
      (libsource (lib "easyedapro") (part "0603WAF2402T5E"))
    )
    (comp (ref "R109")
      (value "2k")
      (footprint "easyedapro:R0603")
      (description "电阻类型:厚膜电阻;阻值:24kΩ;精度:±1%;功率:100mW;工作电压:75V;温度系数:±100ppm/°C;")
      (fields
        (field (name "Manufacturer Part") "0603WAF2402T5E")
        (field (name "Manufacturer") "UNI-ROYAL(厚声)")
      )
      (libsource (lib "easyedapro") (part "0603WAF2402T5E"))
    )
    (comp (ref "U1")
      (value "XL1509-5.0E1")
      (footprint "easyedapro:SOIC-8_L5.0-W4.0-P1.27-LS6.0-BL")
      (description "功能类型:降压型;同步整流:-;输出通道数:-;拓扑结构:-;输入电压:-;输出电流(最大值):-;开关频率:-;")
      (fields (field (name "Manufacturer") "XLSEMI(芯龙)"))
      (libsource (lib "easyedapro") (part "XL1509-5.0E1"))
    )
    (comp (ref "U2")
      (value "1117-3.3")
      (footprint "easyedapro:SOT-223")
      (libsource (lib "easyedapro") (part "LM1117"))
    )
    (comp (ref "U3")
      (value "LTV-357T-C")
      (footprint "easyedapro:SOP-4_L4.4-W3.9-P2.54-LS7.0-TL")
      (fields (field (name "Manufacturer") "LITEON(光宝)"))
      (libsource (lib "easyedapro") (part "LTV-357T-C"))
    )
    (comp (ref "U5")
      (value "GD32F303CCT6")
      (footprint "easyedapro:LQFP48")
      (description "STM32 ARM-based 32-bit MCU with 32 Kbytes Flash, 48-pin LQFP, Industrial Temperature")
      (libsource (lib "easyedapro") (part "STM32F103C6T6"))
    )
    (comp (ref "U7")
      (value "SP3232EEN-L/TR")
      (footprint "easyedapro:SOIC-16_L9.9-W3.9-P1.27-LS6.0-BL")
      (description "类型:收发器;数据速率:235Kbps;")
      (fields (field (name "Manufacturer") "MaxLinear(迈凌)"))
      (libsource (lib "easyedapro") (part "SP3232EEN-L/TR"))
    )
    (comp (ref "U8")
      (value "自弹TF卡座TFAA")
      (footprint "easyedapro:SIM-SMD_C9900015645")
      (libsource (lib "easyedapro") (part "自弹TF卡座TFAA"))
    )
    (comp (ref "U10")
      (value "LTV-357T-C")
      (footprint "easyedapro:SOP-4_L4.4-W3.9-P2.54-LS7.0-TL")
      (fields (field (name "Manufacturer") "LITEON(光宝)"))
      (libsource (lib "easyedapro") (part "LTV-357T-C"))
    )
    (comp (ref "U18")
      (value "LTV-357T-C")
      (footprint "easyedapro:SOP-4_L4.4-W3.9-P2.54-LS7.0-TL")
      (fields (field (name "Manufacturer") "LITEON(光宝)"))
      (libsource (lib "easyedapro") (part "LTV-357T-C"))
    )
    (comp (ref "U20")
      (value "74LVC1G17")
      (footprint "easyedapro:SMD8")
      (libsource (lib "easyedapro") (part "74LVC1G04"))
    )
    (comp (ref "U21")
      (value "LTV-357T-C")
      (footprint "easyedapro:SOP-4_L4.4-W3.9-P2.54-LS7.0-TL")
      (fields (field (name "Manufacturer") "LITEON(光宝)"))
      (libsource (lib "easyedapro") (part "LTV-357T-C"))
    )
    (comp (ref "U23")
      (value "CA-IS3760")
      (footprint "easyedapro:SOIC-16_L9.9-W3.9-P1.27-LS6.0-BL")
      (fields (field (name "Manufacturer") "Chipanalog(川土微)"))
      (libsource (lib "easyedapro") (part "CA-IS3760HN"))
    )
    (comp (ref "U24")
      (value "74LVC1G17")
      (footprint "easyedapro:SMD8")
      (libsource (lib "easyedapro") (part "74LVC1G04"))
    )
    (comp (ref "U25")
      (value "74LVC1G17")
      (footprint "easyedapro:SMD8")
      (libsource (lib "easyedapro") (part "74LVC1G04"))
    )
    (comp (ref "U26")
      (value "CH340G")
      (footprint "easyedapro:SOIC-16_L9.9-W3.9-P1.27-LS6.0-BL")
      (description "应用功能:收发器;接口协议:USB 2.0;数据速率:2Mbps;")
      (fields (field (name "Manufacturer") "WCH(南京沁恒)"))
      (libsource (lib "easyedapro") (part "CH340G"))
    )
    (comp (ref "U27")
      (value "CH376S")
      (footprint "easyedapro:SOIC-28_L17.9-W7.5-P1.27-LS10.3-BL")
      (description "应用功能:-;USB协议版本:USB 2.0;数据速率:12Mbps;")
      (fields (field (name "Manufacturer") "WCH(南京沁恒)"))
      (libsource (lib "easyedapro") (part "CH376S"))
    )
    (comp (ref "U29")
      (value "B0505LS-1WR3")
      (footprint "easyedapro:PWRM-TH_BXXXXLS-1WR3")
      (description "100%国产化器件，高可靠性，具备ROHS、REACH、CE认证产品")
      (fields (field (name "Manufacturer") "DEXU(德旭电子)"))
      (libsource (lib "easyedapro") (part "B0505LS-1WR3_C909800"))
    )
    (comp (ref "U30")
      (value "LTV-357T-C")
      (footprint "easyedapro:SOP-4_L4.4-W3.9-P2.54-LS7.0-TL")
      (fields (field (name "Manufacturer") "LITEON(光宝)"))
      (libsource (lib "easyedapro") (part "LTV-357T-C"))
    )
    (comp (ref "U31")
      (value "74LVC1G17")
      (footprint "easyedapro:SMD8")
      (libsource (lib "easyedapro") (part "74LVC1G04"))
    )
    (comp (ref "USB1")
      (value "U-USBAR04P-F002")
      (footprint "easyedapro:USB-A-TH_USB-302-T")
      (description "连接器类型:Type-A;协议标准:USB 2.0;公母:母;安装方式:弯插;触点数量:4P;端口数量:1;额定电流 - 电源:1.5A;工作温度:0°C~+50°C;")
      (fields (field (name "Manufacturer") "Ckmtw(灿科盟)"))
      (libsource (lib "easyedapro") (part "U-USBAR04P-F001"))
    )
    (comp (ref "USB2")
      (value "TYPE-C 16PIN")
      (footprint "easyedapro:USB-C-SMD_TYPE-C-6PIN-2MD-073")
      (description "连接器类型:Type-C;标准:-;公母:母;端口数量:1;触点数量:16P;安装方式:卧贴;额定电流 - 电源:5A;工作温度范围:-25°C~+85°C;")
      (fields (field (name "Manufacturer") "SHOU HAN(首韩)"))
      (libsource (lib "easyedapro") (part "TYPE-C 16PIN 2MD(073)"))
    )
    (comp (ref "USB7")
      (value "AF 10.0 QT-ZB6.8")
      (footprint "easyedapro:USB-A-SMD_AF-10.0-QT-ZB6.8")
      (description "连接器类型:Type-A;协议标准:USB 2.0;公母:母;安装方式:卧贴;触点数量:4P;端口数量:1;额定电流 - 电源:1.5A;工作温度:-25°C~+85°C;")
      (fields (field (name "Manufacturer") "SHOU HAN(首韩)"))
      (libsource (lib "easyedapro") (part "AF 10.0 QT-ZB6.8"))
    )
    (comp (ref "USB8")
      (value "TYPE-C 16PIN(MC-107SSY)")
      (footprint "easyedapro:USB-TYPE-C-SMD_MC-107SSY")
      (description "连接器类型:Type-C;协议标准:USB 3.1;公母:母;安装方式:卧贴;触点数量:16P;端口数量:1;额定电流 - 电源:5A;工作温度:-25°C~+85°C;")
      (fields (field (name "Manufacturer") "HANBO(汉博)"))
      (libsource (lib "easyedapro") (part "MC-107SSY"))
    )
    (comp (ref "Y1")
      (value "12M")
      (footprint "easyedapro:晶振贴片")
      (description "Crystal Oscillator")
      (libsource (lib "easyedapro") (part "XTAL"))
    )
    (comp (ref "Y2")
      (value "8M")
      (footprint "easyedapro:晶振贴片")
      (description "Crystal Oscillator")
      (libsource (lib "easyedapro") (part "XTAL"))
    )
  )
  (nets
    (net (code "1") (name "/2_EN_O") (class "Default")
      (node (ref "H10") (pin "8") (pinfunction "8_8") (pintype "unspecified"))
      (node (ref "H2") (pin "8") (pinfunction "8_8") (pintype "unspecified"))
      (node (ref "H4") (pin "8") (pinfunction "8_8") (pintype "unspecified"))
      (node (ref "H7") (pin "8") (pinfunction "8_8") (pintype "unspecified"))
    )
    (net (code "2") (name "/340_R") (class "Default")
      (node (ref "D8") (pin "2") (pinfunction "A_2") (pintype "unspecified"))
      (node (ref "R92") (pin "1") (pinfunction "1_1") (pintype "input"))
      (node (ref "U26") (pin "3") (pinfunction "RXD_3") (pintype "unspecified"))
    )
    (net (code "3") (name "/340_T") (class "Default")
      (node (ref "D9") (pin "1") (pinfunction "K_1") (pintype "unspecified"))
      (node (ref "U26") (pin "2") (pinfunction "TXD_2") (pintype "unspecified"))
    )
    (net (code "4") (name "/A_1A") (class "Default")
      (node (ref "H11") (pin "4") (pinfunction "4_4") (pintype "unspecified"))
      (node (ref "P31") (pin "3") (pinfunction "3_3") (pintype "unspecified"))
      (node (ref "R88") (pin "2") (pinfunction "2_2") (pintype "input"))
    )
    (net (code "5") (name "/A_1B") (class "Default")
      (node (ref "H11") (pin "3") (pinfunction "3_3") (pintype "unspecified"))
      (node (ref "P31") (pin "4") (pinfunction "4_4") (pintype "unspecified"))
      (node (ref "R89") (pin "2") (pinfunction "2_2") (pintype "input"))
    )
    (net (code "6") (name "/A_2A") (class "Default")
      (node (ref "H11") (pin "5") (pinfunction "5_5") (pintype "unspecified"))
      (node (ref "P31") (pin "2") (pinfunction "2_2") (pintype "unspecified"))
      (node (ref "R87") (pin "2") (pinfunction "2_2") (pintype "input"))
    )
    (net (code "7") (name "/A_2B") (class "Default")
      (node (ref "H11") (pin "6") (pinfunction "6_6") (pintype "unspecified"))
      (node (ref "P31") (pin "1") (pinfunction "1_1") (pintype "unspecified"))
      (node (ref "R86") (pin "2") (pinfunction "2_2") (pintype "input"))
    )
    (net (code "8") (name "/A_DIR_O") (class "Default")
      (node (ref "H10") (pin "1") (pinfunction "1_1") (pintype "unspecified"))
      (node (ref "U31") (pin "4") (pinfunction "Y_4") (pintype "unspecified"))
    )
    (net (code "9") (name "/A_STEP_O") (class "Default")
      (node (ref "H10") (pin "2") (pinfunction "2_2") (pintype "unspecified"))
      (node (ref "U23") (pin "15") (pinfunction "VO1_15") (pintype "unspecified"))
    )
    (net (code "10") (name "/BOOT0") (class "Default")
      (node (ref "R96") (pin "1") (pinfunction "1_1") (pintype "input"))
      (node (ref "U5") (pin "44") (pinfunction "BOOT0_44") (pintype "input"))
    )
    (net (code "11") (name "/BOOT1") (class "Default")
      (node (ref "R97") (pin "1") (pinfunction "1_1") (pintype "input"))
      (node (ref "U5") (pin "20") (pinfunction "PB2/BOOT1_20") (pintype "bidirectional"))
    )
    (net (code "12") (name "/CC1") (class "Default")
      (node (ref "USB2") (pin "4") (pinfunction "CC1_4") (pintype "unspecified"))
    )
    (net (code "13") (name "/CC2") (class "Default")
      (node (ref "USB2") (pin "10") (pinfunction "CC2_10") (pintype "unspecified"))
    )
    (net (code "14") (name "/D1+") (class "Default")
      (node (ref "D7") (pin "3") (pinfunction "I/O2_3") (pintype "unspecified"))
      (node (ref "USB1") (pin "3") (pinfunction "D+_3") (pintype "unspecified"))
      (node (ref "USB7") (pin "3") (pinfunction "D+_3") (pintype "unspecified"))
    )
    (net (code "15") (name "/D1-") (class "Default")
      (node (ref "D7") (pin "1") (pinfunction "I/O1_1") (pintype "unspecified"))
      (node (ref "USB1") (pin "2") (pinfunction "D-_2") (pintype "unspecified"))
      (node (ref "USB7") (pin "2") (pinfunction "D-_2") (pintype "unspecified"))
    )
    (net (code "16") (name "/DM") (class "Default")
      (node (ref "D24") (pin "6") (pinfunction "I/O1_6") (pintype "unspecified"))
    )
    (net (code "17") (name "/DN_D-") (class "Default")
      (node (ref "U26") (pin "6") (pinfunction "UD-_6") (pintype "unspecified"))
      (node (ref "USB2") (pin "5") (pinfunction "DN2_5") (pintype "unspecified"))
      (node (ref "USB2") (pin "7") (pinfunction "DN1_7") (pintype "unspecified"))
      (node (ref "USB8") (pin "A7") (pinfunction "DN1_A7") (pintype "unspecified"))
      (node (ref "USB8") (pin "B7") (pinfunction "DN2_B7") (pintype "unspecified"))
    )
    (net (code "18") (name "/DP") (class "Default")
      (node (ref "D24") (pin "4") (pinfunction "I/O2_4") (pintype "unspecified"))
    )
    (net (code "19") (name "/DP_D+") (class "Default")
      (node (ref "U26") (pin "5") (pinfunction "UD+_5") (pintype "unspecified"))
      (node (ref "USB2") (pin "6") (pinfunction "DP1_6") (pintype "unspecified"))
      (node (ref "USB2") (pin "8") (pinfunction "DP2_8") (pintype "unspecified"))
      (node (ref "USB8") (pin "A6") (pinfunction "DP1_A6") (pintype "unspecified"))
      (node (ref "USB8") (pin "B6") (pinfunction "DP2_B6") (pintype "unspecified"))
    )
    (net (code "20") (name "/DTR") (class "Default")
      (node (ref "C66") (pin "2") (pinfunction "2_2") (pintype "input"))
      (node (ref "U26") (pin "13") (pinfunction "DTR#_13") (pintype "unspecified"))
    )
    (net (code "21") (name "/EX3") (class "Default")
      (node (ref "U5") (pin "4") (pinfunction "PC15-OSC32_OUT_4") (pintype "bidirectional"))
    )
    (net (code "22") (name "/LASER_LOCATION") (class "Default")
      (node (ref "U5") (pin "19") (pinfunction "PB1_19") (pintype "bidirectional"))
    )
    (net (code "23") (name "/LO") (class "Default")
      (node (ref "U5") (pin "3") (pinfunction "PC14-OSC32_IN_3") (pintype "bidirectional"))
    )
    (net (code "24") (name "/MA_DIR") (class "Default")
      (node (ref "R105") (pin "1") (pinfunction "1_1") (pintype "input"))
      (node (ref "U31") (pin "2") (pinfunction "A_2") (pintype "unspecified"))
      (node (ref "U5") (pin "17") (pinfunction "PA7_17") (pintype "bidirectional"))
    )
    (net (code "25") (name "/MA_STEP") (class "Default")
      (node (ref "U23") (pin "2") (pinfunction "VI1_2") (pintype "unspecified"))
      (node (ref "U5") (pin "16") (pinfunction "PA6_16") (pintype "bidirectional"))
    )
    (net (code "26") (name "/MOTOR_EN") (class "Default")
      (node (ref "R25") (pin "1") (pinfunction "1_1") (pintype "input"))
      (node (ref "U24") (pin "2") (pinfunction "A_2") (pintype "unspecified"))
      (node (ref "U5") (pin "18") (pinfunction "PB0_18") (pintype "bidirectional"))
    )
    (net (code "27") (name "/MX_DIR") (class "Default")
      (node (ref "R24") (pin "1") (pinfunction "1_1") (pintype "input"))
      (node (ref "U25") (pin "2") (pinfunction "A_2") (pintype "unspecified"))
      (node (ref "U5") (pin "10") (pinfunction "PA0-WKUP_10") (pintype "bidirectional"))
    )
    (net (code "28") (name "/MX_STEP") (class "Default")
      (node (ref "U23") (pin "7") (pinfunction "VI6_7") (pintype "unspecified"))
      (node (ref "U5") (pin "11") (pinfunction "PA1_11") (pintype "bidirectional"))
    )
    (net (code "29") (name "/MY_DIR") (class "Default")
      (node (ref "U23") (pin "6") (pinfunction "VI5_6") (pintype "unspecified"))
      (node (ref "U5") (pin "12") (pinfunction "PA2_12") (pintype "bidirectional"))
    )
    (net (code "30") (name "/MY_STEP") (class "Default")
      (node (ref "U23") (pin "5") (pinfunction "VI4_5") (pintype "unspecified"))
      (node (ref "U5") (pin "13") (pinfunction "PA3_13") (pintype "bidirectional"))
    )
    (net (code "31") (name "/MZ_DIR") (class "Default")
      (node (ref "U23") (pin "4") (pinfunction "VI3_4") (pintype "unspecified"))
      (node (ref "U5") (pin "14") (pinfunction "PA4_14") (pintype "bidirectional"))
    )
    (net (code "32") (name "/MZ_STEP") (class "Default")
      (node (ref "U23") (pin "3") (pinfunction "VI2_3") (pintype "unspecified"))
      (node (ref "U5") (pin "15") (pinfunction "PA5_15") (pintype "bidirectional"))
    )
    (net (code "33") (name "/M_EN_O") (class "Default")
      (node (ref "U24") (pin "4") (pinfunction "Y_4") (pintype "unspecified"))
    )
    (net (code "34") (name "/NRST") (class "Default")
      (node (ref "C59") (pin "2") (pinfunction "2_2") (pintype "input"))
      (node (ref "R98") (pin "1") (pinfunction "1_1") (pintype "input"))
      (node (ref "U5") (pin "7") (pinfunction "NRST_7") (pintype "bidirectional"))
    )
    (net (code "35") (name "/PROBE") (class "Default")
      (node (ref "R78") (pin "2") (pinfunction "2_2") (pintype "input"))
      (node (ref "U18") (pin "4") (pinfunction "4_4") (pintype "unspecified"))
      (node (ref "U5") (pin "38") (pinfunction "PA15/JTDI_38") (pintype "bidirectional"))
    )
    (net (code "36") (name "/PROBE_O") (class "Default")
      (node (ref "D26") (pin "2") (pinfunction "2_2") (pintype "input"))
      (node (ref "P22") (pin "1") (pintype "input"))
      (node (ref "U18") (pin "2") (pinfunction "2_2") (pintype "unspecified"))
    )
    (net (code "37") (name "/PWM") (class "Default")
      (node (ref "U20") (pin "2") (pinfunction "A_2") (pintype "unspecified"))
    )
    (net (code "38") (name "/PWM_5V") (class "Default")
      (node (ref "D25") (pin "2") (pinfunction "2_2") (pintype "input"))
      (node (ref "P24") (pin "1") (pinfunction "1_1") (pintype "unspecified"))
      (node (ref "P29") (pin "1") (pinfunction "1_1") (pintype "unspecified"))
      (node (ref "U20") (pin "4") (pinfunction "Y_4") (pintype "unspecified"))
    )
    (net (code "39") (name "/R1IN") (class "Default")
      (node (ref "H13") (pin "2") (pinfunction "2_2") (pintype "unspecified"))
      (node (ref "U7") (pin "13") (pinfunction "R1IN_13") (pintype "unspecified"))
    )
    (net (code "40") (name "/R1OUT") (class "Default")
      (node (ref "U7") (pin "12") (pinfunction "R1OUT_12") (pintype "unspecified"))
    )
    (net (code "41") (name "/R2IN") (class "Default")
      (node (ref "P35") (pin "2") (pinfunction "D-_2") (pintype "unspecified"))
      (node (ref "U7") (pin "8") (pinfunction "R2IN_8") (pintype "unspecified"))
    )
    (net (code "42") (name "/R2OUT") (class "Default")
      (node (ref "R101") (pin "1") (pinfunction "1_1") (pintype "input"))
      (node (ref "U7") (pin "9") (pinfunction "R2OUT_9") (pintype "unspecified"))
    )
    (net (code "43") (name "/RS232_VCC") (class "Default")
      (node (ref "C65") (pin "2") (pinfunction "2_2") (pintype "input"))
      (node (ref "R103") (pin "1") (pinfunction "1_1") (pintype "input"))
      (node (ref "R104") (pin "1") (pinfunction "1_1") (pintype "input"))
      (node (ref "U7") (pin "16") (pinfunction "VCC_16") (pintype "unspecified"))
    )
    (net (code "44") (name "/RST") (class "Default")
      (node (ref "C66") (pin "1") (pinfunction "1_1") (pintype "input"))
      (node (ref "U5") (pin "42") (pinfunction "PB6_42") (pintype "bidirectional"))
    )
    (net (code "45") (name "/RXD0") (class "Default")
      (node (ref "H9") (pin "1") (pinfunction "1_1") (pintype "unspecified"))
    )
    (net (code "46") (name "/RXD1") (class "Default")
      (node (ref "D9") (pin "2") (pinfunction "A_2") (pintype "unspecified"))
      (node (ref "H9") (pin "4") (pinfunction "4_4") (pintype "unspecified"))
      (node (ref "R91") (pin "1") (pinfunction "1_1") (pintype "input"))
      (node (ref "U5") (pin "31") (pinfunction "PA10_31") (pintype "bidirectional"))
    )
    (net (code "47") (name "/RXD3") (class "Default")
      (node (ref "R101") (pin "2") (pinfunction "2_2") (pintype "input"))
      (node (ref "U5") (pin "22") (pinfunction "PB11_22") (pintype "bidirectional"))
    )
    (net (code "48") (name "/SAFETY_DOOR") (class "Default")
      (node (ref "U5") (pin "45") (pinfunction "PB8_45") (pintype "bidirectional"))
    )
    (net (code "49") (name "/SD_CD") (class "Default")
      (node (ref "R30") (pin "1") (pinfunction "1_1") (pintype "unspecified"))
      (node (ref "U8") (pin "9") (pinfunction "CD_9") (pintype "unspecified"))
    )
    (net (code "50") (name "/SD_CS") (class "Default")
      (node (ref "R27") (pin "1") (pinfunction "1_1") (pintype "unspecified"))
      (node (ref "U8") (pin "2") (pinfunction "CD_2") (pintype "unspecified"))
    )
    (net (code "51") (name "/SD_MISO") (class "Default")
      (node (ref "R29") (pin "1") (pinfunction "1_1") (pintype "unspecified"))
      (node (ref "U8") (pin "7") (pinfunction "DAT0_7") (pintype "unspecified"))
    )
    (net (code "52") (name "/SD_MOSI") (class "Default")
      (node (ref "R28") (pin "1") (pinfunction "1_1") (pintype "unspecified"))
      (node (ref "U8") (pin "3") (pinfunction "CMD_3") (pintype "unspecified"))
    )
    (net (code "53") (name "/SD_SCLK") (class "Default")
      (node (ref "U8") (pin "5") (pinfunction "CLX_5") (pintype "unspecified"))
    )
    (net (code "54") (name "/SL_D+") (class "Default")
      (node (ref "D24") (pin "3") (pinfunction "I/O2_3") (pintype "unspecified"))
    )
    (net (code "55") (name "/SL_D-") (class "Default")
      (node (ref "D24") (pin "1") (pinfunction "I/O1_1") (pintype "unspecified"))
    )
    (net (code "56") (name "/SPI1_CS") (class "Default")
      (node (ref "U27") (pin "18") (pinfunction "SCS/D3_18") (pintype "unspecified"))
    )
    (net (code "57") (name "/SPI1_MISO") (class "Default")
      (node (ref "U27") (pin "22") (pinfunction "SDO/D7_22") (pintype "unspecified"))
      (node (ref "U5") (pin "40") (pinfunction "PB4/JNTRST_40") (pintype "bidirectional"))
    )
    (net (code "58") (name "/SPI1_MOSI") (class "Default")
      (node (ref "U27") (pin "21") (pinfunction "SDI/D6_21") (pintype "unspecified"))
      (node (ref "U5") (pin "41") (pinfunction "PB5_41") (pintype "bidirectional"))
    )
    (net (code "59") (name "/SPI1_SCK") (class "Default")
      (node (ref "U27") (pin "20") (pinfunction "SCK/D5_20") (pintype "unspecified"))
      (node (ref "U5") (pin "39") (pinfunction "PB3/JTDO_39") (pintype "bidirectional"))
    )
    (net (code "60") (name "/SPINDLE_DIR") (class "Default")
      (node (ref "U5") (pin "27") (pinfunction "PB14_27") (pintype "bidirectional"))
    )
    (net (code "61") (name "/SPINDLE_EN") (class "Default")
      (node (ref "U5") (pin "26") (pinfunction "PB13_26") (pintype "bidirectional"))
    )
    (net (code "62") (name "/SPINDLE_PWM") (class "Default")
      (node (ref "U5") (pin "29") (pinfunction "PA8_29") (pintype "bidirectional"))
    )
    (net (code "63") (name "/SWCLK") (class "Default")
      (node (ref "H12") (pin "3") (pinfunction "3_3") (pintype "unspecified"))
      (node (ref "U5") (pin "37") (pinfunction "PA14/JTCK/SWCLK_37") (pintype "bidirectional"))
    )
    (net (code "64") (name "/SWDIO") (class "Default")
      (node (ref "H12") (pin "4") (pinfunction "4_4") (pintype "unspecified"))
      (node (ref "U5") (pin "34") (pinfunction "PA13/JTMS/SWDIO_34") (pintype "bidirectional"))
    )
    (net (code "65") (name "/T1IN") (class "Default")
      (node (ref "U7") (pin "11") (pinfunction "T1IN_11") (pintype "unspecified"))
    )
    (net (code "66") (name "/T1OUT") (class "Default")
      (node (ref "H13") (pin "3") (pinfunction "3_3") (pintype "unspecified"))
      (node (ref "U7") (pin "14") (pinfunction "T1OUT_14") (pintype "unspecified"))
    )
    (net (code "67") (name "/T2IN") (class "Default")
      (node (ref "R102") (pin "1") (pinfunction "1_1") (pintype "input"))
      (node (ref "U7") (pin "10") (pinfunction "T2IN_10") (pintype "unspecified"))
    )
    (net (code "68") (name "/T2OUT") (class "Default")
      (node (ref "P35") (pin "3") (pinfunction "D+_3") (pintype "unspecified"))
      (node (ref "U7") (pin "7") (pinfunction "T2OUT_7") (pintype "unspecified"))
    )
    (net (code "69") (name "/TXD0") (class "Default")
      (node (ref "H9") (pin "2") (pinfunction "2_2") (pintype "unspecified"))
    )
    (net (code "70") (name "/TXD1") (class "Default")
      (node (ref "D8") (pin "1") (pinfunction "K_1") (pintype "unspecified"))
      (node (ref "H9") (pin "3") (pinfunction "3_3") (pintype "unspecified"))
      (node (ref "U5") (pin "30") (pinfunction "PA9_30") (pintype "bidirectional"))
    )
    (net (code "71") (name "/TXD3") (class "Default")
      (node (ref "R102") (pin "2") (pinfunction "2_2") (pintype "input"))
      (node (ref "U5") (pin "21") (pinfunction "PB10_21") (pintype "bidirectional"))
    )
    (net (code "72") (name "/USB_D+") (class "Default")
      (node (ref "D7") (pin "4") (pinfunction "I/O2_4") (pintype "unspecified"))
    )
    (net (code "73") (name "/USB_D-") (class "Default")
      (node (ref "D7") (pin "6") (pinfunction "I/O1_6") (pintype "unspecified"))
    )
    (net (code "74") (name "/VUSB") (class "Default")
      (node (ref "D24") (pin "5") (pinfunction "VBUS_5") (pintype "unspecified"))
    )
    (net (code "75") (name "/XTAL1") (class "Default")
      (node (ref "C58") (pin "2") (pinfunction "2_2") (pintype "input"))
      (node (ref "U5") (pin "5") (pinfunction "OSC_IN/PD0_5") (pintype "input"))
      (node (ref "Y2") (pin "1") (pinfunction "OSC1_1") (pintype "unspecified"))
    )
    (net (code "76") (name "/XTAL2") (class "Default")
      (node (ref "C57") (pin "2") (pinfunction "2_2") (pintype "input"))
      (node (ref "U5") (pin "6") (pinfunction "OSC_OUT/PD1_6") (pintype "output"))
      (node (ref "Y2") (pin "2") (pinfunction "OSC2_2") (pintype "unspecified"))
    )
    (net (code "77") (name "/X_1A") (class "Default")
      (node (ref "H3") (pin "4") (pinfunction "4_4") (pintype "unspecified"))
      (node (ref "P18") (pin "3") (pinfunction "3_3") (pintype "unspecified"))
      (node (ref "R63") (pin "2") (pinfunction "2_2") (pintype "input"))
    )
    (net (code "78") (name "/X_1B") (class "Default")
      (node (ref "H3") (pin "3") (pinfunction "3_3") (pintype "unspecified"))
      (node (ref "P18") (pin "4") (pinfunction "4_4") (pintype "unspecified"))
      (node (ref "R64") (pin "2") (pinfunction "2_2") (pintype "input"))
    )
    (net (code "79") (name "/X_2A") (class "Default")
      (node (ref "H3") (pin "5") (pinfunction "5_5") (pintype "unspecified"))
      (node (ref "P18") (pin "2") (pinfunction "2_2") (pintype "unspecified"))
      (node (ref "R62") (pin "2") (pinfunction "2_2") (pintype "input"))
    )
    (net (code "80") (name "/X_2B") (class "Default")
      (node (ref "H3") (pin "6") (pinfunction "6_6") (pintype "unspecified"))
      (node (ref "P18") (pin "1") (pinfunction "1_1") (pintype "unspecified"))
      (node (ref "R61") (pin "2") (pinfunction "2_2") (pintype "input"))
    )
    (net (code "81") (name "/X_DIR_O") (class "Default")
      (node (ref "H2") (pin "1") (pinfunction "1_1") (pintype "unspecified"))
      (node (ref "U25") (pin "4") (pinfunction "Y_4") (pintype "unspecified"))
    )
    (net (code "82") (name "/X_LIMT") (class "Default")
      (node (ref "R85") (pin "2") (pinfunction "2_2") (pintype "input"))
      (node (ref "U3") (pin "4") (pinfunction "4_4") (pintype "unspecified"))
      (node (ref "U5") (pin "25") (pinfunction "PB12_25") (pintype "bidirectional"))
    )
    (net (code "83") (name "/X_LIMT_I") (class "Default")
      (node (ref "P30") (pin "1") (pinfunction "1_1") (pintype "unspecified"))
      (node (ref "P8") (pin "1") (pinfunction "1_1") (pintype "unspecified"))
      (node (ref "U3") (pin "2") (pinfunction "2_2") (pintype "unspecified"))
    )
    (net (code "84") (name "/X_STEP_O") (class "Default")
      (node (ref "H2") (pin "2") (pinfunction "2_2") (pintype "unspecified"))
      (node (ref "U23") (pin "10") (pinfunction "VO6_10") (pintype "unspecified"))
    )
    (net (code "85") (name "/Y_1A") (class "Default")
      (node (ref "H5") (pin "4") (pinfunction "4_4") (pintype "unspecified"))
      (node (ref "P21") (pin "3") (pinfunction "3_3") (pintype "unspecified"))
      (node (ref "P36") (pin "3") (pinfunction "3_3") (pintype "unspecified"))
      (node (ref "R108") (pin "2") (pinfunction "2_2") (pintype "input"))
      (node (ref "R67") (pin "2") (pinfunction "2_2") (pintype "input"))
    )
    (net (code "86") (name "/Y_1B") (class "Default")
      (node (ref "H5") (pin "3") (pinfunction "3_3") (pintype "unspecified"))
      (node (ref "P21") (pin "4") (pinfunction "4_4") (pintype "unspecified"))
      (node (ref "P36") (pin "4") (pinfunction "4_4") (pintype "unspecified"))
      (node (ref "R109") (pin "2") (pinfunction "2_2") (pintype "input"))
      (node (ref "R68") (pin "2") (pinfunction "2_2") (pintype "input"))
    )
    (net (code "87") (name "/Y_2A") (class "Default")
      (node (ref "H5") (pin "5") (pinfunction "5_5") (pintype "unspecified"))
      (node (ref "P21") (pin "2") (pinfunction "2_2") (pintype "unspecified"))
      (node (ref "P36") (pin "2") (pinfunction "2_2") (pintype "unspecified"))
      (node (ref "R107") (pin "2") (pinfunction "2_2") (pintype "input"))
      (node (ref "R66") (pin "2") (pinfunction "2_2") (pintype "input"))
    )
    (net (code "88") (name "/Y_2B") (class "Default")
      (node (ref "H5") (pin "6") (pinfunction "6_6") (pintype "unspecified"))
      (node (ref "P21") (pin "1") (pinfunction "1_1") (pintype "unspecified"))
      (node (ref "P36") (pin "1") (pinfunction "1_1") (pintype "unspecified"))
      (node (ref "R106") (pin "2") (pinfunction "2_2") (pintype "input"))
      (node (ref "R65") (pin "2") (pinfunction "2_2") (pintype "input"))
    )
    (net (code "89") (name "/Y_DIR_O") (class "Default")
      (node (ref "H4") (pin "1") (pinfunction "1_1") (pintype "unspecified"))
      (node (ref "U23") (pin "11") (pinfunction "VO5_11") (pintype "unspecified"))
    )
    (net (code "90") (name "/Y_LIMT") (class "Default")
      (node (ref "R84") (pin "2") (pinfunction "2_2") (pintype "input"))
      (node (ref "U21") (pin "4") (pinfunction "4_4") (pintype "unspecified"))
      (node (ref "U5") (pin "28") (pinfunction "PB15_28") (pintype "bidirectional"))
    )
    (net (code "91") (name "/Y_LIMT_I") (class "Default")
      (node (ref "P11") (pin "1") (pinfunction "1_1") (pintype "unspecified"))
      (node (ref "P12") (pin "1") (pinfunction "1_1") (pintype "unspecified"))
      (node (ref "U21") (pin "2") (pinfunction "2_2") (pintype "unspecified"))
    )
    (net (code "92") (name "/Y_STEP_O") (class "Default")
      (node (ref "H4") (pin "2") (pinfunction "2_2") (pintype "unspecified"))
      (node (ref "U23") (pin "12") (pinfunction "VO4_12") (pintype "unspecified"))
    )
    (net (code "93") (name "/Z_1A") (class "Default")
      (node (ref "H8") (pin "4") (pinfunction "4_4") (pintype "unspecified"))
      (node (ref "P23") (pin "3") (pinfunction "3_3") (pintype "unspecified"))
      (node (ref "R71") (pin "2") (pinfunction "2_2") (pintype "input"))
    )
    (net (code "94") (name "/Z_1B") (class "Default")
      (node (ref "H8") (pin "3") (pinfunction "3_3") (pintype "unspecified"))
      (node (ref "P23") (pin "4") (pinfunction "4_4") (pintype "unspecified"))
      (node (ref "R72") (pin "2") (pinfunction "2_2") (pintype "input"))
    )
    (net (code "95") (name "/Z_2A") (class "Default")
      (node (ref "H8") (pin "5") (pinfunction "5_5") (pintype "unspecified"))
      (node (ref "P23") (pin "2") (pinfunction "2_2") (pintype "unspecified"))
      (node (ref "R70") (pin "2") (pinfunction "2_2") (pintype "input"))
    )
    (net (code "96") (name "/Z_2B") (class "Default")
      (node (ref "H8") (pin "6") (pinfunction "6_6") (pintype "unspecified"))
      (node (ref "P23") (pin "1") (pinfunction "1_1") (pintype "unspecified"))
      (node (ref "R69") (pin "2") (pinfunction "2_2") (pintype "input"))
    )
    (net (code "97") (name "/Z_DIR_O") (class "Default")
      (node (ref "H7") (pin "1") (pinfunction "1_1") (pintype "unspecified"))
      (node (ref "U23") (pin "13") (pinfunction "VO3_13") (pintype "unspecified"))
    )
    (net (code "98") (name "/Z_LIMT") (class "Default")
      (node (ref "R83") (pin "2") (pinfunction "2_2") (pintype "input"))
      (node (ref "U10") (pin "4") (pinfunction "4_4") (pintype "unspecified"))
    )
    (net (code "99") (name "/Z_LIMT_I") (class "Default")
      (node (ref "P14") (pin "1") (pinfunction "1_1") (pintype "unspecified"))
      (node (ref "P16") (pin "1") (pinfunction "1_1") (pintype "unspecified"))
      (node (ref "U10") (pin "2") (pinfunction "2_2") (pintype "unspecified"))
    )
    (net (code "100") (name "/Z_STEP_O") (class "Default")
      (node (ref "H7") (pin "2") (pinfunction "2_2") (pintype "unspecified"))
      (node (ref "U23") (pin "14") (pinfunction "VO2_14") (pintype "unspecified"))
    )
    (net (code "101") (name "3V3") (class "Default")
      (node (ref "C27") (pin "2") (pinfunction "2_2") (pintype "unspecified"))
      (node (ref "C47") (pin "2") (pinfunction "2_2") (pintype "input"))
      (node (ref "C51") (pin "1") (pinfunction "1_1") (pintype "input"))
      (node (ref "H12") (pin "2") (pinfunction "2_2") (pintype "unspecified"))
      (node (ref "R100") (pin "1") (pinfunction "1_1") (pintype "input"))
      (node (ref "R104") (pin "2") (pinfunction "2_2") (pintype "input"))
      (node (ref "R27") (pin "2") (pinfunction "2_2") (pintype "unspecified"))
      (node (ref "R28") (pin "2") (pinfunction "2_2") (pintype "unspecified"))
      (node (ref "R29") (pin "2") (pinfunction "2_2") (pintype "unspecified"))
      (node (ref "R30") (pin "2") (pinfunction "2_2") (pintype "unspecified"))
      (node (ref "R78") (pin "1") (pinfunction "1_1") (pintype "input"))
      (node (ref "R83") (pin "1") (pinfunction "1_1") (pintype "input"))
      (node (ref "R84") (pin "1") (pinfunction "1_1") (pintype "input"))
      (node (ref "R85") (pin "1") (pinfunction "1_1") (pintype "input"))
      (node (ref "R91") (pin "2") (pinfunction "2_2") (pintype "input"))
      (node (ref "R98") (pin "2") (pinfunction "2_2") (pintype "input"))
      (node (ref "U2") (pin "2") (pinfunction "OUT_2") (pintype "unspecified"))
      (node (ref "U2") (pin "4") (pinfunction "=_4") (pintype "unspecified"))
      (node (ref "U23") (pin "1") (pinfunction "VDDA_1") (pintype "unspecified"))
      (node (ref "U5") (pin "24") (pinfunction "VDD_1_24") (pintype "unspecified"))
      (node (ref "U5") (pin "36") (pinfunction "VDD_2_36") (pintype "unspecified"))
      (node (ref "U5") (pin "48") (pinfunction "VDD_3_48") (pintype "unspecified"))
      (node (ref "U5") (pin "9") (pinfunction "VDDA_9") (pintype "unspecified"))
      (node (ref "U8") (pin "4") (pinfunction "VDD_4") (pintype "unspecified"))
    )
    (net (code "102") (name "5V_2") (class "Default")
      (node (ref "H10") (pin "5") (pinfunction "5_5") (pintype "unspecified"))
      (node (ref "H10") (pin "6") (pinfunction "6_6") (pintype "unspecified"))
      (node (ref "H10") (pin "7") (pinfunction "7_7") (pintype "unspecified"))
      (node (ref "H11") (pin "2") (pinfunction "2_2") (pintype "unspecified"))
      (node (ref "H2") (pin "5") (pinfunction "5_5") (pintype "unspecified"))
      (node (ref "H2") (pin "6") (pinfunction "6_6") (pintype "unspecified"))
      (node (ref "H2") (pin "7") (pinfunction "7_7") (pintype "unspecified"))
      (node (ref "H3") (pin "2") (pinfunction "2_2") (pintype "unspecified"))
      (node (ref "H4") (pin "5") (pinfunction "5_5") (pintype "unspecified"))
      (node (ref "H4") (pin "6") (pinfunction "6_6") (pintype "unspecified"))
      (node (ref "H4") (pin "7") (pinfunction "7_7") (pintype "unspecified"))
      (node (ref "H5") (pin "2") (pinfunction "2_2") (pintype "unspecified"))
      (node (ref "H7") (pin "5") (pinfunction "5_5") (pintype "unspecified"))
      (node (ref "H7") (pin "6") (pinfunction "6_6") (pintype "unspecified"))
      (node (ref "H7") (pin "7") (pinfunction "7_7") (pintype "unspecified"))
      (node (ref "H8") (pin "2") (pinfunction "2_2") (pintype "unspecified"))
    )
    (net (code "103") (name "5V_MCU") (class "Default")
      (node (ref "C2") (pin "2") (pinfunction "2_2") (pintype "input"))
      (node (ref "C3") (pin "2") (pinfunction "2_2") (pintype "input"))
      (node (ref "U29") (pin "6") (pinfunction "+VO_6") (pintype "unspecified"))
    )
    (net (code "104") (name "5V_USB") (class "Default")
      (node (ref "R21") (pin "1") (pinfunction "1_1") (pintype "unspecified"))
      (node (ref "R90") (pin "1") (pinfunction "1_1") (pintype "input"))
      (node (ref "USB2") (pin "11") (pinfunction "VBUS_11") (pintype "unspecified"))
      (node (ref "USB2") (pin "2") (pinfunction "VBUS_2") (pintype "unspecified"))
    )
    (net (code "105") (name "5V_VCC") (class "Default")
      (node (ref "C35") (pin "2") (pinfunction "2_2") (pintype "unspecified"))
      (node (ref "C39") (pin "2") (pinfunction "2_2") (pintype "unspecified"))
      (node (ref "C41") (pin "2") (pinfunction "2_2") (pintype "unspecified"))
      (node (ref "C42") (pin "2") (pinfunction "2_2") (pintype "unspecified"))
      (node (ref "C43") (pin "2") (pinfunction "2_2") (pintype "unspecified"))
      (node (ref "C54") (pin "1") (pinfunction "1_1") (pintype "input"))
      (node (ref "C61") (pin "2") (pinfunction "2_2") (pintype "input"))
      (node (ref "C67") (pin "2") (pinfunction "2_2") (pintype "unspecified"))
      (node (ref "C7") (pin "1") (pinfunction "1_1") (pintype "input"))
      (node (ref "C8") (pin "1") (pinfunction "1_1") (pintype "input"))
      (node (ref "D4") (pin "2") (pinfunction "2_2") (pintype "input"))
      (node (ref "D7") (pin "5") (pinfunction "VBUS_5") (pintype "unspecified"))
      (node (ref "L1") (pin "1") (pinfunction "1_1") (pintype "unspecified"))
      (node (ref "R103") (pin "2") (pinfunction "2_2") (pintype "input"))
      (node (ref "R58") (pin "2") (pinfunction "2_2") (pintype "input"))
      (node (ref "R77") (pin "1") (pinfunction "1_1") (pintype "input"))
      (node (ref "R90") (pin "2") (pinfunction "2_2") (pintype "input"))
      (node (ref "R92") (pin "2") (pinfunction "2_2") (pintype "input"))
      (node (ref "U1") (pin "3") (pinfunction "FB_3") (pintype "input"))
      (node (ref "U2") (pin "3") (pinfunction "IN_3") (pintype "unspecified"))
      (node (ref "U20") (pin "5") (pinfunction "VCC_5") (pintype "unspecified"))
      (node (ref "U23") (pin "16") (pinfunction "VDDB_16") (pintype "unspecified"))
      (node (ref "U24") (pin "5") (pinfunction "VCC_5") (pintype "unspecified"))
      (node (ref "U25") (pin "5") (pinfunction "VCC_5") (pintype "unspecified"))
      (node (ref "U26") (pin "16") (pinfunction "VCC_16") (pintype "unspecified"))
      (node (ref "U29") (pin "1") (pinfunction "VIN_1") (pintype "unspecified"))
      (node (ref "U31") (pin "5") (pinfunction "VCC_5") (pintype "unspecified"))
      (node (ref "USB1") (pin "1") (pinfunction "VCC_1") (pintype "unspecified"))
      (node (ref "USB7") (pin "1") (pinfunction "VCC_1") (pintype "unspecified"))
    )
    (net (code "106") (name "24V_D1") (class "Default")
      (node (ref "C1") (pin "1") (pintype "unspecified"))
      (node (ref "C38") (pin "1") (pinfunction "1_1") (pintype "unspecified"))
      (node (ref "D1") (pin "2") (pinfunction "2_2") (pintype "unspecified"))
      (node (ref "P11") (pin "2") (pinfunction "2_2") (pintype "unspecified"))
      (node (ref "P12") (pin "2") (pinfunction "2_2") (pintype "unspecified"))
      (node (ref "P14") (pin "2") (pinfunction "2_2") (pintype "unspecified"))
      (node (ref "P16") (pin "2") (pinfunction "2_2") (pintype "unspecified"))
      (node (ref "P24") (pin "2") (pinfunction "2_2") (pintype "unspecified"))
      (node (ref "P30") (pin "2") (pinfunction "2_2") (pintype "unspecified"))
      (node (ref "P8") (pin "2") (pinfunction "2_2") (pintype "unspecified"))
      (node (ref "R60") (pin "2") (pinfunction "2_2") (pintype "input"))
      (node (ref "R79") (pin "1") (pinfunction "1_1") (pintype "input"))
      (node (ref "R81") (pin "1") (pinfunction "1_1") (pintype "input"))
      (node (ref "R82") (pin "1") (pinfunction "1_1") (pintype "input"))
      (node (ref "U1") (pin "1") (pinfunction "VIN_1") (pintype "input"))
    )
    (net (code "107") (name "24V_D2") (class "Default")
      (node (ref "C19") (pin "1") (pintype "unspecified"))
      (node (ref "C32") (pin "1") (pintype "unspecified"))
      (node (ref "C34") (pin "1") (pintype "unspecified"))
      (node (ref "C40") (pin "1") (pintype "unspecified"))
      (node (ref "D33") (pin "2") (pinfunction "2_2") (pintype "unspecified"))
      (node (ref "H11") (pin "8") (pinfunction "8_8") (pintype "unspecified"))
      (node (ref "H3") (pin "8") (pinfunction "8_8") (pintype "unspecified"))
      (node (ref "H5") (pin "8") (pinfunction "8_8") (pintype "unspecified"))
      (node (ref "H8") (pin "8") (pinfunction "8_8") (pintype "unspecified"))
    )
    (net (code "108") (name "24V_OUT") (class "Default")
      (node (ref "D6") (pin "2") (pinfunction "2_2") (pintype "unspecified"))
      (node (ref "P35") (pin "1") (pinfunction "VBUS_1") (pintype "unspecified"))
    )
    (net (code "109") (name "GND") (class "Default")
      (node (ref "C1") (pin "2") (pintype "unspecified"))
      (node (ref "C19") (pin "2") (pintype "unspecified"))
      (node (ref "C27") (pin "1") (pinfunction "1_1") (pintype "unspecified"))
      (node (ref "C32") (pin "2") (pintype "unspecified"))
      (node (ref "C34") (pin "2") (pintype "unspecified"))
      (node (ref "C35") (pin "1") (pinfunction "1_1") (pintype "unspecified"))
      (node (ref "C36") (pin "1") (pinfunction "1_1") (pintype "input"))
      (node (ref "C38") (pin "2") (pinfunction "2_2") (pintype "unspecified"))
      (node (ref "C39") (pin "1") (pinfunction "1_1") (pintype "unspecified"))
      (node (ref "C40") (pin "2") (pintype "unspecified"))
      (node (ref "C41") (pin "1") (pinfunction "1_1") (pintype "unspecified"))
      (node (ref "C42") (pin "1") (pinfunction "1_1") (pintype "unspecified"))
      (node (ref "C43") (pin "1") (pinfunction "1_1") (pintype "unspecified"))
      (node (ref "C47") (pin "1") (pinfunction "1_1") (pintype "input"))
      (node (ref "C51") (pin "2") (pinfunction "2_2") (pintype "input"))
      (node (ref "C52") (pin "1") (pinfunction "1_1") (pintype "input"))
      (node (ref "C54") (pin "2") (pinfunction "2_2") (pintype "input"))
      (node (ref "C55") (pin "2") (pinfunction "2_2") (pintype "input"))
      (node (ref "C56") (pin "1") (pinfunction "1_1") (pintype "input"))
      (node (ref "C57") (pin "1") (pinfunction "1_1") (pintype "input"))
      (node (ref "C58") (pin "1") (pinfunction "1_1") (pintype "input"))
      (node (ref "C59") (pin "1") (pinfunction "1_1") (pintype "input"))
      (node (ref "C64") (pin "2") (pinfunction "2_2") (pintype "input"))
      (node (ref "C65") (pin "1") (pinfunction "1_1") (pintype "input"))
      (node (ref "C67") (pin "1") (pinfunction "1_1") (pintype "unspecified"))
      (node (ref "C7") (pin "2") (pinfunction "2_2") (pintype "input"))
      (node (ref "C8") (pin "2") (pinfunction "2_2") (pintype "input"))
      (node (ref "D24") (pin "2") (pinfunction "GND_2") (pintype "unspecified"))
      (node (ref "D25") (pin "1") (pinfunction "1_1") (pintype "input"))
      (node (ref "D26") (pin "1") (pinfunction "1_1") (pintype "input"))
      (node (ref "D32") (pin "1") (pinfunction "1_1") (pintype "unspecified"))
      (node (ref "D4") (pin "1") (pinfunction "1_1") (pintype "input"))
      (node (ref "D7") (pin "2") (pinfunction "GND_2") (pintype "unspecified"))
      (node (ref "DC1") (pin "2") (pinfunction "2_2") (pintype "unspecified"))
      (node (ref "DC1") (pin "3") (pinfunction "3_3") (pintype "unspecified"))
      (node (ref "H11") (pin "1") (pinfunction "1_1") (pintype "unspecified"))
      (node (ref "H11") (pin "7") (pinfunction "7_7") (pintype "unspecified"))
      (node (ref "H12") (pin "1") (pinfunction "1_1") (pintype "unspecified"))
      (node (ref "H13") (pin "4") (pinfunction "4_4") (pintype "unspecified"))
      (node (ref "H3") (pin "1") (pinfunction "1_1") (pintype "unspecified"))
      (node (ref "H3") (pin "7") (pinfunction "7_7") (pintype "unspecified"))
      (node (ref "H5") (pin "1") (pinfunction "1_1") (pintype "unspecified"))
      (node (ref "H5") (pin "7") (pinfunction "7_7") (pintype "unspecified"))
      (node (ref "H8") (pin "1") (pinfunction "1_1") (pintype "unspecified"))
      (node (ref "H8") (pin "7") (pinfunction "7_7") (pintype "unspecified"))
      (node (ref "LED2") (pin "1") (pinfunction "K_1") (pintype "unspecified"))
      (node (ref "LED3") (pin "1") (pinfunction "K_1") (pintype "unspecified"))
      (node (ref "LED5") (pin "1") (pinfunction "K_1") (pintype "unspecified"))
      (node (ref "P11") (pin "3") (pinfunction "3_3") (pintype "unspecified"))
      (node (ref "P12") (pin "3") (pinfunction "3_3") (pintype "unspecified"))
      (node (ref "P14") (pin "3") (pinfunction "3_3") (pintype "unspecified"))
      (node (ref "P16") (pin "3") (pinfunction "3_3") (pintype "unspecified"))
      (node (ref "P22") (pin "2") (pintype "input"))
      (node (ref "P24") (pin "3") (pinfunction "3_3") (pintype "unspecified"))
      (node (ref "P29") (pin "3") (pinfunction "3_3") (pintype "unspecified"))
      (node (ref "P30") (pin "3") (pinfunction "3_3") (pintype "unspecified"))
      (node (ref "P35") (pin "4") (pinfunction "GND_4") (pintype "unspecified"))
      (node (ref "P35") (pin "5") (pinfunction "GND_5") (pintype "unspecified"))
      (node (ref "P35") (pin "6") (pinfunction "GND_6") (pintype "unspecified"))
      (node (ref "P8") (pin "3") (pinfunction "3_3") (pintype "unspecified"))
      (node (ref "R105") (pin "2") (pinfunction "2_2") (pintype "input"))
      (node (ref "R106") (pin "1") (pinfunction "1_1") (pintype "input"))
      (node (ref "R107") (pin "1") (pinfunction "1_1") (pintype "input"))
      (node (ref "R108") (pin "1") (pinfunction "1_1") (pintype "input"))
      (node (ref "R109") (pin "1") (pinfunction "1_1") (pintype "input"))
      (node (ref "R24") (pin "2") (pinfunction "2_2") (pintype "input"))
      (node (ref "R25") (pin "2") (pinfunction "2_2") (pintype "input"))
      (node (ref "R59") (pin "1") (pinfunction "1_1") (pintype "input"))
      (node (ref "R61") (pin "1") (pinfunction "1_1") (pintype "input"))
      (node (ref "R62") (pin "1") (pinfunction "1_1") (pintype "input"))
      (node (ref "R63") (pin "1") (pinfunction "1_1") (pintype "input"))
      (node (ref "R64") (pin "1") (pinfunction "1_1") (pintype "input"))
      (node (ref "R65") (pin "1") (pinfunction "1_1") (pintype "input"))
      (node (ref "R66") (pin "1") (pinfunction "1_1") (pintype "input"))
      (node (ref "R67") (pin "1") (pinfunction "1_1") (pintype "input"))
      (node (ref "R68") (pin "1") (pinfunction "1_1") (pintype "input"))
      (node (ref "R69") (pin "1") (pinfunction "1_1") (pintype "input"))
      (node (ref "R70") (pin "1") (pinfunction "1_1") (pintype "input"))
      (node (ref "R71") (pin "1") (pinfunction "1_1") (pintype "input"))
      (node (ref "R72") (pin "1") (pinfunction "1_1") (pintype "input"))
      (node (ref "R86") (pin "1") (pinfunction "1_1") (pintype "input"))
      (node (ref "R87") (pin "1") (pinfunction "1_1") (pintype "input"))
      (node (ref "R88") (pin "1") (pinfunction "1_1") (pintype "input"))
      (node (ref "R89") (pin "1") (pinfunction "1_1") (pintype "input"))
      (node (ref "R96") (pin "2") (pinfunction "2_2") (pintype "input"))
      (node (ref "R97") (pin "2") (pinfunction "2_2") (pintype "input"))
      (node (ref "U1") (pin "5") (pinfunction "GND_5") (pintype "input"))
      (node (ref "U1") (pin "6") (pinfunction "GND_6") (pintype "input"))
      (node (ref "U1") (pin "7") (pinfunction "GND_7") (pintype "input"))
      (node (ref "U1") (pin "8") (pinfunction "GND_8") (pintype "input"))
      (node (ref "U10") (pin "3") (pinfunction "3_3") (pintype "unspecified"))
      (node (ref "U18") (pin "3") (pinfunction "3_3") (pintype "unspecified"))
      (node (ref "U2") (pin "1") (pinfunction "GND_1") (pintype "unspecified"))
      (node (ref "U20") (pin "3") (pinfunction "GND_3") (pintype "unspecified"))
      (node (ref "U21") (pin "3") (pinfunction "3_3") (pintype "unspecified"))
      (node (ref "U23") (pin "8") (pinfunction "GNDA_8") (pintype "unspecified"))
      (node (ref "U23") (pin "9") (pinfunction "GNDB_9") (pintype "unspecified"))
      (node (ref "U24") (pin "3") (pinfunction "GND_3") (pintype "unspecified"))
      (node (ref "U25") (pin "3") (pinfunction "GND_3") (pintype "unspecified"))
      (node (ref "U26") (pin "1") (pinfunction "GND_1") (pintype "unspecified"))
      (node (ref "U3") (pin "3") (pinfunction "3_3") (pintype "unspecified"))
      (node (ref "U30") (pin "2") (pinfunction "2_2") (pintype "unspecified"))
      (node (ref "U31") (pin "3") (pinfunction "GND_3") (pintype "unspecified"))
      (node (ref "U5") (pin "23") (pinfunction "VSS_1_23") (pintype "unspecified"))
      (node (ref "U5") (pin "35") (pinfunction "VSS_2_35") (pintype "unspecified"))
      (node (ref "U5") (pin "47") (pinfunction "VSS_3_47") (pintype "unspecified"))
      (node (ref "U5") (pin "8") (pinfunction "VSSA_8") (pintype "unspecified"))
      (node (ref "U7") (pin "15") (pinfunction "GND_15") (pintype "unspecified"))
      (node (ref "U8") (pin "10") (pinfunction "GND_10") (pintype "unspecified"))
      (node (ref "U8") (pin "11") (pinfunction "GND_11") (pintype "unspecified"))
      (node (ref "U8") (pin "12") (pinfunction "GND_12") (pintype "unspecified"))
      (node (ref "U8") (pin "13") (pinfunction "GND_13") (pintype "unspecified"))
      (node (ref "U8") (pin "6") (pinfunction "VSS_6") (pintype "unspecified"))
      (node (ref "USB1") (pin "4") (pinfunction "GND_4") (pintype "unspecified"))
      (node (ref "USB1") (pin "5") (pinfunction "SH1_5") (pintype "unspecified"))
      (node (ref "USB1") (pin "6") (pinfunction "SH2_6") (pintype "unspecified"))
      (node (ref "USB2") (pin "1") (pinfunction "GND_1") (pintype "unspecified"))
      (node (ref "USB2") (pin "12") (pinfunction "GND_12") (pintype "unspecified"))
      (node (ref "USB2") (pin "13") (pinfunction "SHELL_13") (pintype "unspecified"))
      (node (ref "USB2") (pin "14") (pinfunction "SHELL_14") (pintype "unspecified"))
      (node (ref "USB7") (pin "4") (pinfunction "GND_4") (pintype "unspecified"))
      (node (ref "USB7") (pin "5") (pinfunction "EH_5") (pintype "unspecified"))
    )
    (net (code "110") (name "Net-(H2-Pad3)") (class "Default")
      (node (ref "H2") (pin "3") (pinfunction "3_3") (pintype "unspecified"))
      (node (ref "H2") (pin "4") (pinfunction "4_4") (pintype "unspecified"))
    )
    (net (code "111") (name "Net-(H4-Pad3)") (class "Default")
      (node (ref "H4") (pin "3") (pinfunction "3_3") (pintype "unspecified"))
      (node (ref "H4") (pin "4") (pinfunction "4_4") (pintype "unspecified"))
    )
    (net (code "112") (name "Net-(H7-Pad3)") (class "Default")
      (node (ref "H7") (pin "3") (pinfunction "3_3") (pintype "unspecified"))
      (node (ref "H7") (pin "4") (pinfunction "4_4") (pintype "unspecified"))
    )
    (net (code "113") (name "Net-(H10-Pad3)") (class "Default")
      (node (ref "H10") (pin "3") (pinfunction "3_3") (pintype "unspecified"))
      (node (ref "H10") (pin "4") (pinfunction "4_4") (pintype "unspecified"))
    )
    (net (code "114") (name "Net-(LED2-A)") (class "Default")
      (node (ref "LED2") (pin "2") (pinfunction "A_2") (pintype "unspecified"))
      (node (ref "R58") (pin "1") (pinfunction "1_1") (pintype "input"))
    )
    (net (code "115") (name "Net-(LED3-A)") (class "Default")
      (node (ref "LED3") (pin "2") (pinfunction "A_2") (pintype "unspecified"))
      (node (ref "R60") (pin "1") (pinfunction "1_1") (pintype "input"))
    )
    (net (code "116") (name "Net-(LED5-A)") (class "Default")
      (node (ref "LED5") (pin "2") (pinfunction "A_2") (pintype "unspecified"))
      (node (ref "R21") (pin "2") (pinfunction "2_2") (pintype "unspecified"))
    )
    (net (code "117") (name "Net-(R77-Pad2)") (class "Default")
      (node (ref "R77") (pin "2") (pinfunction "2_2") (pintype "input"))
      (node (ref "U18") (pin "1") (pinfunction "1_1") (pintype "unspecified"))
    )
    (net (code "118") (name "Net-(R79-Pad2)") (class "Default")
      (node (ref "R79") (pin "2") (pinfunction "2_2") (pintype "input"))
      (node (ref "U10") (pin "1") (pinfunction "1_1") (pintype "unspecified"))
    )
    (net (code "119") (name "Net-(R81-Pad2)") (class "Default")
      (node (ref "R81") (pin "2") (pinfunction "2_2") (pintype "input"))
      (node (ref "U21") (pin "1") (pinfunction "1_1") (pintype "unspecified"))
    )
    (net (code "120") (name "Net-(R82-Pad2)") (class "Default")
      (node (ref "R82") (pin "2") (pinfunction "2_2") (pintype "input"))
      (node (ref "U3") (pin "1") (pinfunction "1_1") (pintype "unspecified"))
    )
    (net (code "121") (name "Net-(R100-Pad2)") (class "Default")
      (node (ref "R100") (pin "2") (pinfunction "2_2") (pintype "input"))
      (node (ref "U30") (pin "1") (pinfunction "1_1") (pintype "unspecified"))
    )
    (net (code "122") (name "Net-(U1-ON{slash}OFF)") (class "Default")
      (node (ref "R59") (pin "2") (pinfunction "2_2") (pintype "input"))
      (node (ref "U1") (pin "4") (pinfunction "ON/OFF_4") (pintype "input"))
    )
    (net (code "123") (name "Net-(U1-OUTPUT)") (class "Default")
      (node (ref "D32") (pin "2") (pinfunction "2_2") (pintype "unspecified"))
      (node (ref "L1") (pin "2") (pinfunction "2_2") (pintype "unspecified"))
      (node (ref "U1") (pin "2") (pinfunction "OUTPUT_2") (pintype "input"))
    )
    (net (code "124") (name "Net-(U7-C1+)") (class "Default")
      (node (ref "C62") (pin "1") (pinfunction "1_1") (pintype "input"))
      (node (ref "U7") (pin "1") (pinfunction "C1+_1") (pintype "unspecified"))
    )
    (net (code "125") (name "Net-(U7-C1-)") (class "Default")
      (node (ref "C62") (pin "2") (pinfunction "2_2") (pintype "input"))
      (node (ref "U7") (pin "3") (pinfunction "C1-_3") (pintype "unspecified"))
    )
    (net (code "126") (name "Net-(U7-C2+)") (class "Default")
      (node (ref "C63") (pin "1") (pinfunction "1_1") (pintype "input"))
      (node (ref "U7") (pin "4") (pinfunction "C2+_4") (pintype "unspecified"))
    )
    (net (code "127") (name "Net-(U7-C2-)") (class "Default")
      (node (ref "C63") (pin "2") (pinfunction "2_2") (pintype "input"))
      (node (ref "U7") (pin "5") (pinfunction "C2-_5") (pintype "unspecified"))
    )
    (net (code "128") (name "Net-(U7-V+)") (class "Default")
      (node (ref "C52") (pin "2") (pinfunction "2_2") (pintype "input"))
      (node (ref "U7") (pin "2") (pinfunction "V+_2") (pintype "unspecified"))
    )
    (net (code "129") (name "Net-(U7-V-)") (class "Default")
      (node (ref "C64") (pin "1") (pinfunction "1_1") (pintype "input"))
      (node (ref "U7") (pin "6") (pinfunction "V-_6") (pintype "unspecified"))
    )
    (net (code "130") (name "Net-(U26-V3)") (class "Default")
      (node (ref "C55") (pin "1") (pinfunction "1_1") (pintype "input"))
      (node (ref "U26") (pin "4") (pinfunction "V3_4") (pintype "unspecified"))
    )
    (net (code "131") (name "Net-(U26-XI)") (class "Default")
      (node (ref "C36") (pin "2") (pinfunction "2_2") (pintype "input"))
      (node (ref "U26") (pin "7") (pinfunction "XI_7") (pintype "unspecified"))
      (node (ref "Y1") (pin "2") (pinfunction "OSC2_2") (pintype "unspecified"))
    )
    (net (code "132") (name "Net-(U26-XO)") (class "Default")
      (node (ref "C56") (pin "2") (pinfunction "2_2") (pintype "input"))
      (node (ref "U26") (pin "8") (pinfunction "XO_8") (pintype "unspecified"))
      (node (ref "Y1") (pin "1") (pinfunction "OSC1_1") (pintype "unspecified"))
    )
    (net (code "133") (name "PGND") (class "Default")
      (node (ref "C61") (pin "1") (pinfunction "1_1") (pintype "input"))
      (node (ref "U29") (pin "2") (pinfunction "GND_2") (pintype "unspecified"))
    )
    (net (code "134") (name "SGND") (class "Default")
      (node (ref "C2") (pin "1") (pinfunction "1_1") (pintype "input"))
      (node (ref "C3") (pin "1") (pinfunction "1_1") (pintype "input"))
      (node (ref "U29") (pin "4") (pinfunction "0V_4") (pintype "unspecified"))
    )
    (net (code "135") (name "VIN24V") (class "Default")
      (node (ref "D1") (pin "1") (pinfunction "1_1") (pintype "unspecified"))
      (node (ref "D33") (pin "1") (pinfunction "1_1") (pintype "unspecified"))
      (node (ref "D6") (pin "1") (pinfunction "1_1") (pintype "unspecified"))
      (node (ref "DC1") (pin "1") (pinfunction "1_1") (pintype "unspecified"))
      (node (ref "H13") (pin "1") (pinfunction "1_1") (pintype "unspecified"))
    )
    (net (code "136") (name "unconnected-(C44-Pad1)") (class "Default")
      (node (ref "C44") (pin "1") (pinfunction "1_1") (pintype "input"))
    )
    (net (code "137") (name "unconnected-(C44-Pad2)") (class "Default")
      (node (ref "C44") (pin "2") (pinfunction "2_2") (pintype "input"))
    )
    (net (code "138") (name "unconnected-(P29-Pad2)") (class "Default")
      (node (ref "P29") (pin "2") (pinfunction "2_2") (pintype "unspecified+no_connect"))
    )
    (net (code "139") (name "unconnected-(R12-Pad1)") (class "Default")
      (node (ref "R12") (pin "1") (pinfunction "1_1") (pintype "unspecified"))
    )
    (net (code "140") (name "unconnected-(R12-Pad2)") (class "Default")
      (node (ref "R12") (pin "2") (pinfunction "2_2") (pintype "unspecified"))
    )
    (net (code "141") (name "unconnected-(U5-PA11-Pad32)") (class "Default")
      (node (ref "U5") (pin "32") (pinfunction "PA11_32") (pintype "bidirectional"))
    )
    (net (code "142") (name "unconnected-(U5-PA12-Pad33)") (class "Default")
      (node (ref "U5") (pin "33") (pinfunction "PA12_33") (pintype "bidirectional"))
    )
    (net (code "143") (name "unconnected-(U5-PB7-Pad43)") (class "Default")
      (node (ref "U5") (pin "43") (pinfunction "PB7_43") (pintype "bidirectional"))
    )
    (net (code "144") (name "unconnected-(U5-PB9-Pad46)") (class "Default")
      (node (ref "U5") (pin "46") (pinfunction "PB9_46") (pintype "bidirectional"))
    )
    (net (code "145") (name "unconnected-(U5-PC13-TAMPER-RTC-Pad2)") (class "Default")
      (node (ref "U5") (pin "2") (pinfunction "PC13-TAMPER-RTC_2") (pintype "bidirectional"))
    )
    (net (code "146") (name "unconnected-(U5-VBAT-Pad1)") (class "Default")
      (node (ref "U5") (pin "1") (pinfunction "VBAT_1") (pintype "unspecified"))
    )
    (net (code "147") (name "unconnected-(U8-DAT1-Pad8)") (class "Default")
      (node (ref "U8") (pin "8") (pinfunction "DAT1_8") (pintype "unspecified"))
    )
    (net (code "148") (name "unconnected-(U8-DAT2-Pad1)") (class "Default")
      (node (ref "U8") (pin "1") (pinfunction "DAT2_1") (pintype "unspecified"))
    )
    (net (code "149") (name "unconnected-(U20-NC-Pad1)") (class "Default")
      (node (ref "U20") (pin "1") (pinfunction "NC_1") (pintype "unspecified"))
    )
    (net (code "150") (name "unconnected-(U24-NC-Pad1)") (class "Default")
      (node (ref "U24") (pin "1") (pinfunction "NC_1") (pintype "unspecified"))
    )
    (net (code "151") (name "unconnected-(U25-NC-Pad1)") (class "Default")
      (node (ref "U25") (pin "1") (pinfunction "NC_1") (pintype "unspecified"))
    )
    (net (code "152") (name "unconnected-(U26-CTS#-Pad9)") (class "Default")
      (node (ref "U26") (pin "9") (pinfunction "CTS#_9") (pintype "unspecified"))
    )
    (net (code "153") (name "unconnected-(U26-DCD#-Pad12)") (class "Default")
      (node (ref "U26") (pin "12") (pinfunction "DCD#_12") (pintype "unspecified"))
    )
    (net (code "154") (name "unconnected-(U26-DSR#-Pad10)") (class "Default")
      (node (ref "U26") (pin "10") (pinfunction "DSR#_10") (pintype "unspecified"))
    )
    (net (code "155") (name "unconnected-(U26-R232-Pad15)") (class "Default")
      (node (ref "U26") (pin "15") (pinfunction "R232_15") (pintype "unspecified"))
    )
    (net (code "156") (name "unconnected-(U26-RI#-Pad11)") (class "Default")
      (node (ref "U26") (pin "11") (pinfunction "RI#_11") (pintype "unspecified"))
    )
    (net (code "157") (name "unconnected-(U26-RTS#-Pad14)") (class "Default")
      (node (ref "U26") (pin "14") (pinfunction "RTS#_14") (pintype "unspecified"))
    )
    (net (code "158") (name "unconnected-(U27-A0-Pad8)") (class "Default")
      (node (ref "U27") (pin "8") (pinfunction "A0_8") (pintype "unspecified"))
    )
    (net (code "159") (name "unconnected-(U27-ACT#-Pad24)") (class "Default")
      (node (ref "U27") (pin "24") (pinfunction "ACT#_24") (pintype "unspecified"))
    )
    (net (code "160") (name "unconnected-(U27-BZ{slash}D4-Pad19)") (class "Default")
      (node (ref "U27") (pin "19") (pinfunction "BZ/D4_19") (pintype "unspecified"))
    )
    (net (code "161") (name "unconnected-(U27-D0-Pad15)") (class "Default")
      (node (ref "U27") (pin "15") (pinfunction "D0_15") (pintype "unspecified"))
    )
    (net (code "162") (name "unconnected-(U27-D1-Pad16)") (class "Default")
      (node (ref "U27") (pin "16") (pinfunction "D1_16") (pintype "unspecified"))
    )
    (net (code "163") (name "unconnected-(U27-D2-Pad17)") (class "Default")
      (node (ref "U27") (pin "17") (pinfunction "D2_17") (pintype "unspecified"))
    )
    (net (code "164") (name "unconnected-(U27-GND-Pad12)") (class "Default")
      (node (ref "U27") (pin "12") (pinfunction "GND_12") (pintype "unspecified"))
    )
    (net (code "165") (name "unconnected-(U27-INT#-Pad1)") (class "Default")
      (node (ref "U27") (pin "1") (pinfunction "INT#_1") (pintype "unspecified"))
    )
    (net (code "166") (name "unconnected-(U27-PCS#-Pad27)") (class "Default")
      (node (ref "U27") (pin "27") (pinfunction "PCS#_27") (pintype "unspecified"))
    )
    (net (code "167") (name "unconnected-(U27-RD#-Pad4)") (class "Default")
      (node (ref "U27") (pin "4") (pinfunction "RD#_4") (pintype "unspecified"))
    )
    (net (code "168") (name "unconnected-(U27-RSTI-Pad2)") (class "Default")
      (node (ref "U27") (pin "2") (pinfunction "RSTI_2") (pintype "unspecified"))
    )
    (net (code "169") (name "unconnected-(U27-RXD-Pad6)") (class "Default")
      (node (ref "U27") (pin "6") (pinfunction "RXD_6") (pintype "unspecified"))
    )
    (net (code "170") (name "unconnected-(U27-SD-CK-Pad26)") (class "Default")
      (node (ref "U27") (pin "26") (pinfunction "SD-CK_26") (pintype "unspecified"))
    )
    (net (code "171") (name "unconnected-(U27-SD-CS-Pad23)") (class "Default")
      (node (ref "U27") (pin "23") (pinfunction "SD-CS_23") (pintype "unspecified"))
    )
    (net (code "172") (name "unconnected-(U27-SD-DO-Pad25)") (class "Default")
      (node (ref "U27") (pin "25") (pinfunction "SD-DO_25") (pintype "unspecified"))
    )
    (net (code "173") (name "unconnected-(U27-SD_DI-Pad7)") (class "Default")
      (node (ref "U27") (pin "7") (pinfunction "SD_DI_7") (pintype "unspecified"))
    )
    (net (code "174") (name "unconnected-(U27-TXD-Pad5)") (class "Default")
      (node (ref "U27") (pin "5") (pinfunction "TXD_5") (pintype "unspecified"))
    )
    (net (code "175") (name "unconnected-(U27-UD+-Pad10)") (class "Default")
      (node (ref "U27") (pin "10") (pinfunction "UD+_10") (pintype "unspecified"))
    )
    (net (code "176") (name "unconnected-(U27-UD--Pad11)") (class "Default")
      (node (ref "U27") (pin "11") (pinfunction "UD-_11") (pintype "unspecified"))
    )
    (net (code "177") (name "unconnected-(U27-V3-Pad9)") (class "Default")
      (node (ref "U27") (pin "9") (pinfunction "V3_9") (pintype "unspecified"))
    )
    (net (code "178") (name "unconnected-(U27-VCC-Pad28)") (class "Default")
      (node (ref "U27") (pin "28") (pinfunction "VCC_28") (pintype "unspecified"))
    )
    (net (code "179") (name "unconnected-(U27-WR#-Pad3)") (class "Default")
      (node (ref "U27") (pin "3") (pinfunction "WR#_3") (pintype "unspecified"))
    )
    (net (code "180") (name "unconnected-(U27-XI-Pad13)") (class "Default")
      (node (ref "U27") (pin "13") (pinfunction "XI_13") (pintype "unspecified"))
    )
    (net (code "181") (name "unconnected-(U27-XO-Pad14)") (class "Default")
      (node (ref "U27") (pin "14") (pinfunction "XO_14") (pintype "unspecified"))
    )
    (net (code "182") (name "unconnected-(U30-Pad3)") (class "Default")
      (node (ref "U30") (pin "3") (pinfunction "3_3") (pintype "unspecified"))
    )
    (net (code "183") (name "unconnected-(U30-Pad4)") (class "Default")
      (node (ref "U30") (pin "4") (pinfunction "4_4") (pintype "unspecified"))
    )
    (net (code "184") (name "unconnected-(U31-NC-Pad1)") (class "Default")
      (node (ref "U31") (pin "1") (pinfunction "NC_1") (pintype "unspecified"))
    )
    (net (code "185") (name "unconnected-(USB2-SBU1-Pad9)") (class "Default")
      (node (ref "USB2") (pin "9") (pinfunction "SBU1_9") (pintype "unspecified+no_connect"))
    )
    (net (code "186") (name "unconnected-(USB2-SBU2-Pad3)") (class "Default")
      (node (ref "USB2") (pin "3") (pinfunction "SBU2_3") (pintype "unspecified+no_connect"))
    )
    (net (code "187") (name "unconnected-(USB8-CC1-PadA5)") (class "Default")
      (node (ref "USB8") (pin "A5") (pinfunction "CC1_A5") (pintype "unspecified"))
    )
    (net (code "188") (name "unconnected-(USB8-CC2-PadB5)") (class "Default")
      (node (ref "USB8") (pin "B5") (pinfunction "CC2_B5") (pintype "unspecified"))
    )
    (net (code "189") (name "unconnected-(USB8-GND-PadA1B12)") (class "Default")
      (node (ref "USB8") (pin "A1B12") (pinfunction "GND_A1B12") (pintype "unspecified"))
    )
    (net (code "190") (name "unconnected-(USB8-GND-PadB1A12)") (class "Default")
      (node (ref "USB8") (pin "B1A12") (pinfunction "GND_B1A12") (pintype "unspecified"))
    )
    (net (code "191") (name "unconnected-(USB8-Pad1)") (class "Default")
      (node (ref "USB8") (pin "1") (pinfunction "1_1") (pintype "unspecified"))
    )
    (net (code "192") (name "unconnected-(USB8-Pad2)") (class "Default")
      (node (ref "USB8") (pin "2") (pinfunction "2_2") (pintype "unspecified"))
    )
    (net (code "193") (name "unconnected-(USB8-Pad3)") (class "Default")
      (node (ref "USB8") (pin "3") (pinfunction "3_3") (pintype "unspecified"))
    )
    (net (code "194") (name "unconnected-(USB8-Pad4)") (class "Default")
      (node (ref "USB8") (pin "4") (pinfunction "4_4") (pintype "unspecified"))
    )
    (net (code "195") (name "unconnected-(USB8-SBU1-PadA8)") (class "Default")
      (node (ref "USB8") (pin "A8") (pinfunction "SBU1_A8") (pintype "unspecified"))
    )
    (net (code "196") (name "unconnected-(USB8-SBU2-PadB8)") (class "Default")
      (node (ref "USB8") (pin "B8") (pinfunction "SBU2_B8") (pintype "unspecified"))
    )
    (net (code "197") (name "unconnected-(USB8-VBUS-PadA4B9)") (class "Default")
      (node (ref "USB8") (pin "A4B9") (pinfunction "VBUS_A4B9") (pintype "unspecified"))
    )
    (net (code "198") (name "unconnected-(USB8-VBUS-PadB4A9)") (class "Default")
      (node (ref "USB8") (pin "B4A9") (pinfunction "VBUS_B4A9") (pintype "unspecified"))
    )
  )
)
